# key_pads_sch_V3.net
KiCad netlist of a schematic drawn in Altium Designer
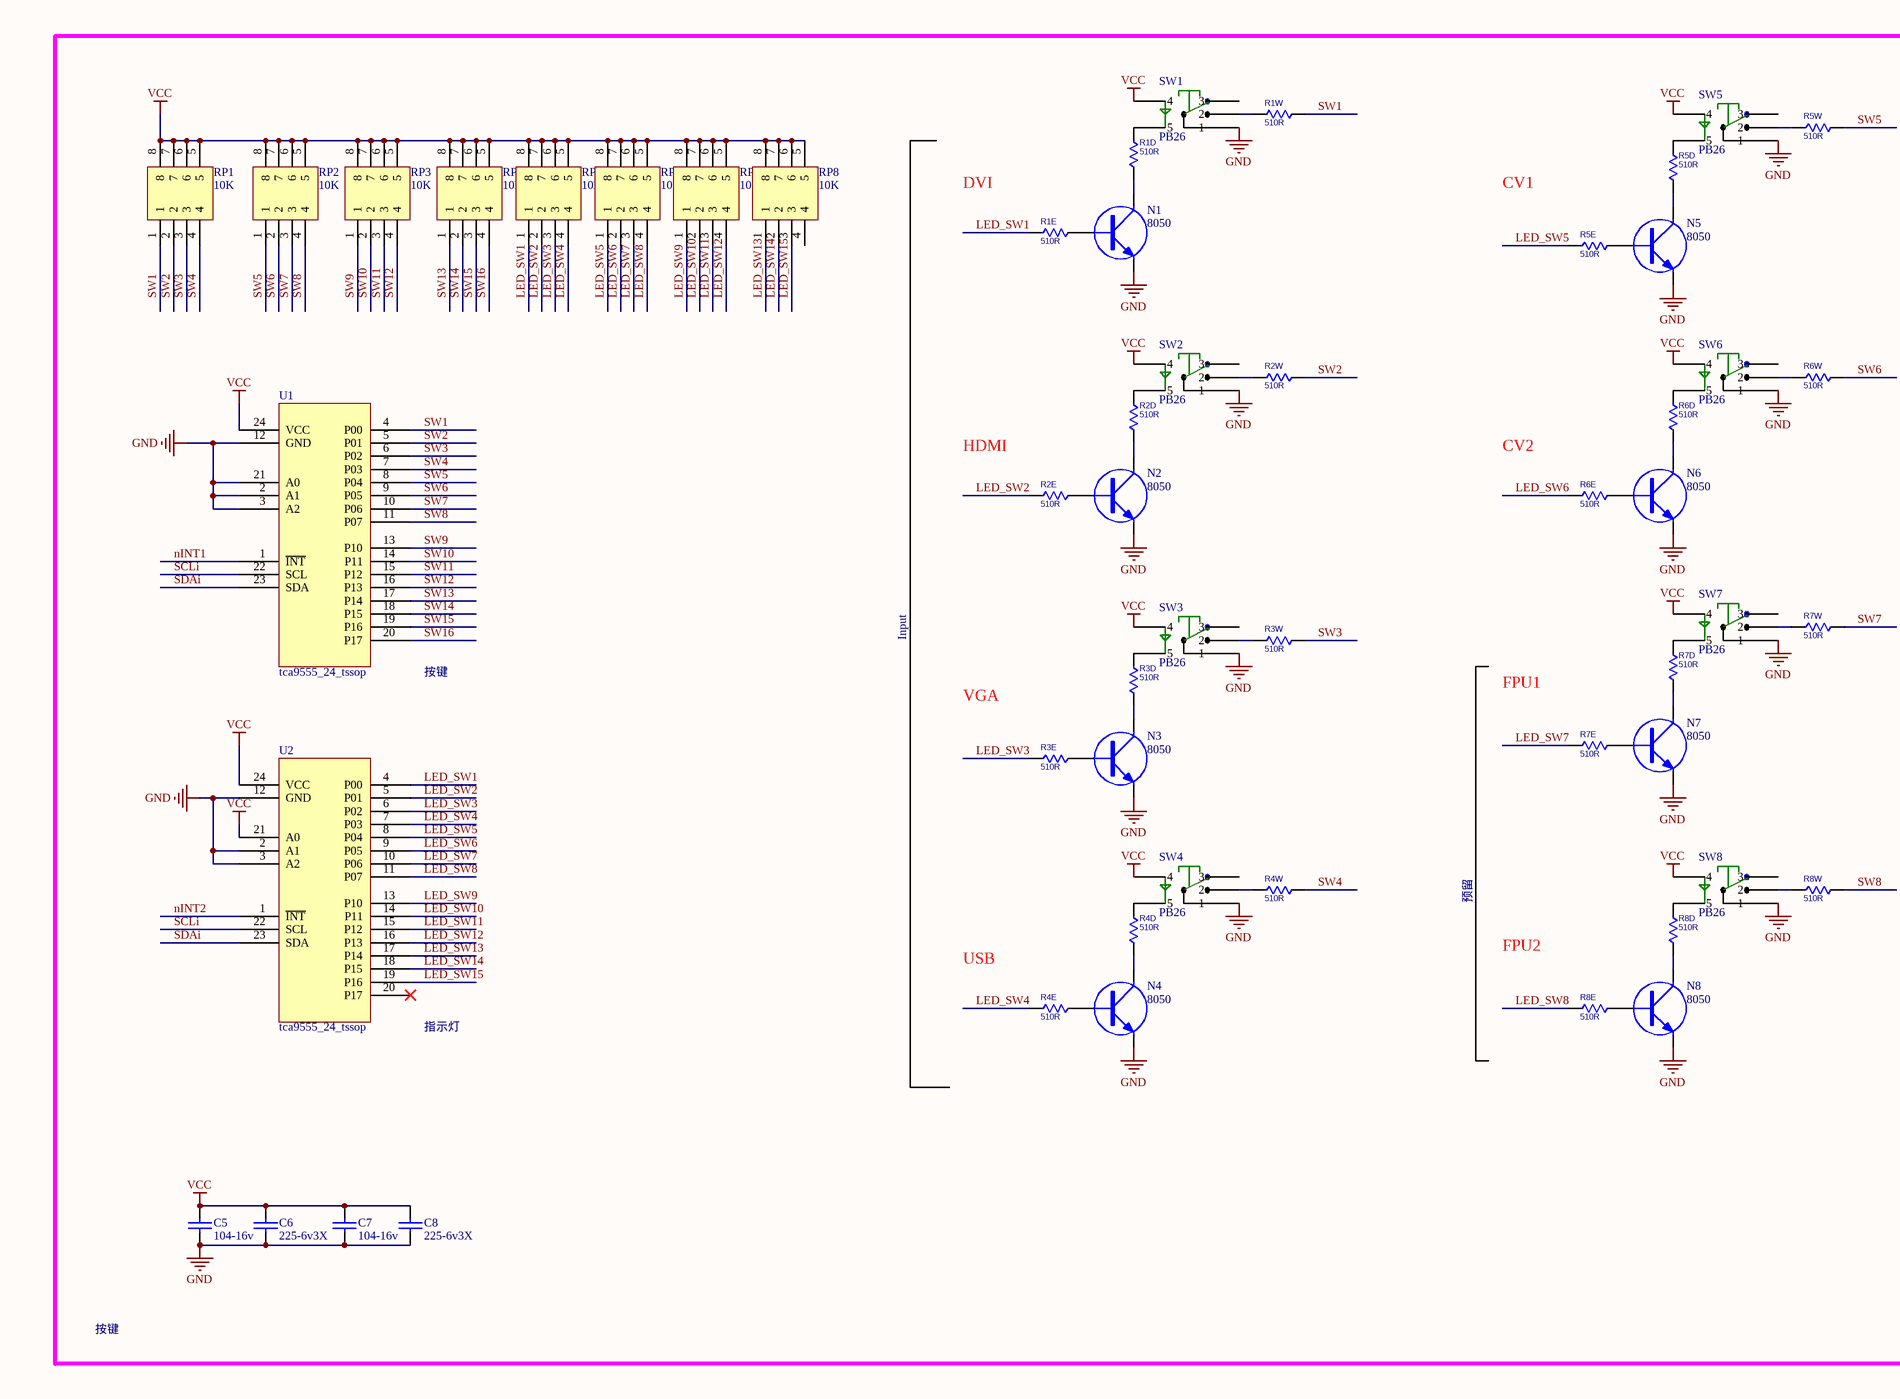
[diagram p0: key_pads_sch_V3.SchDoc, top left]
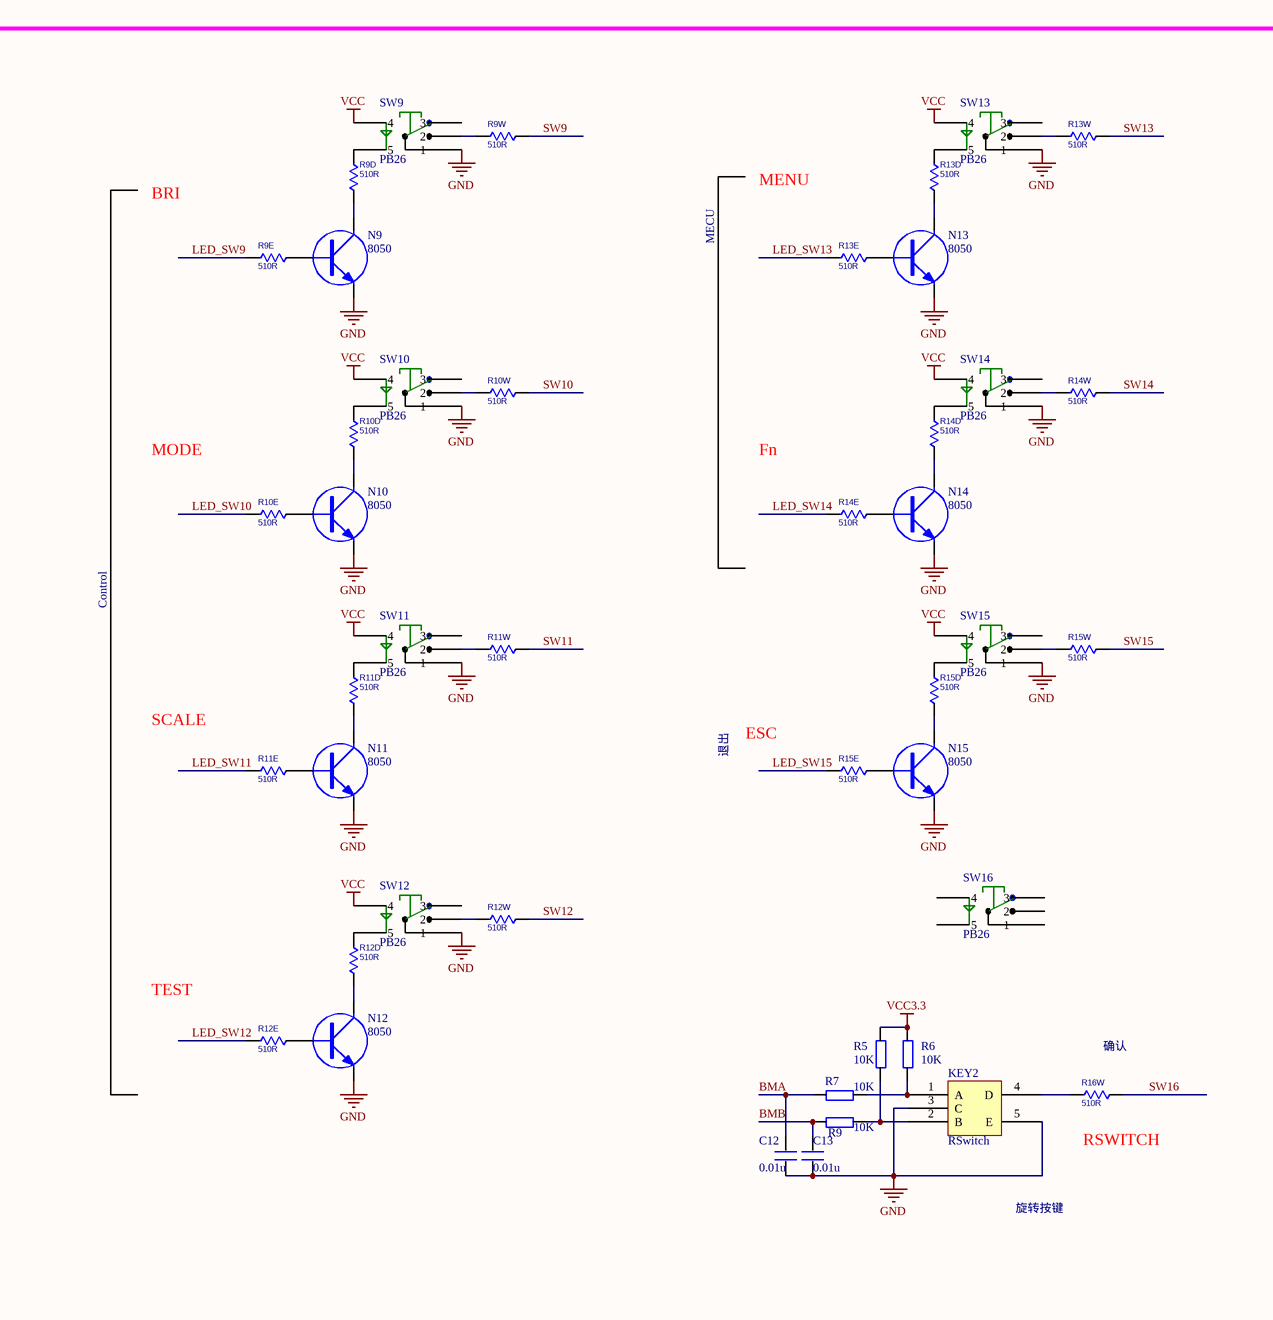
[diagram p1: key_pads_sch_V3.SchDoc, top right]
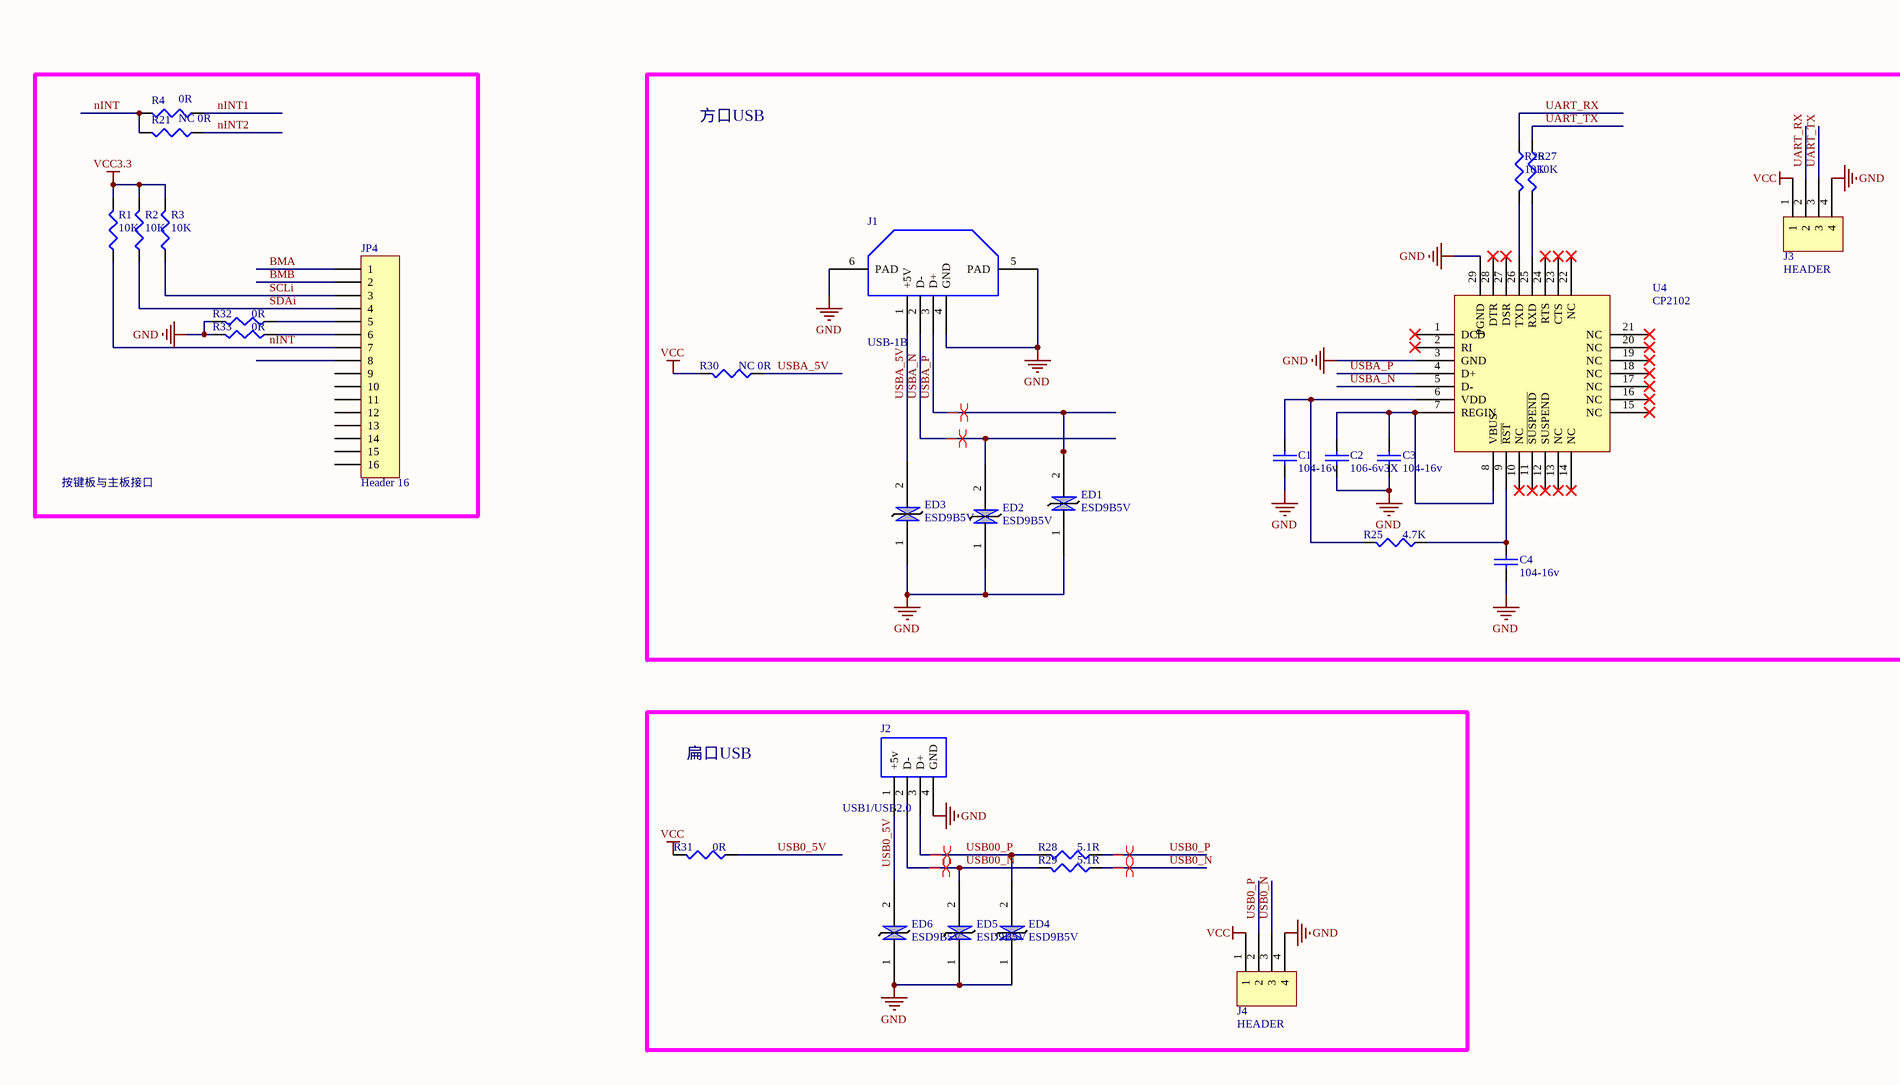
[diagram p2: key_pads_sch_V3.SchDoc, bottom left]
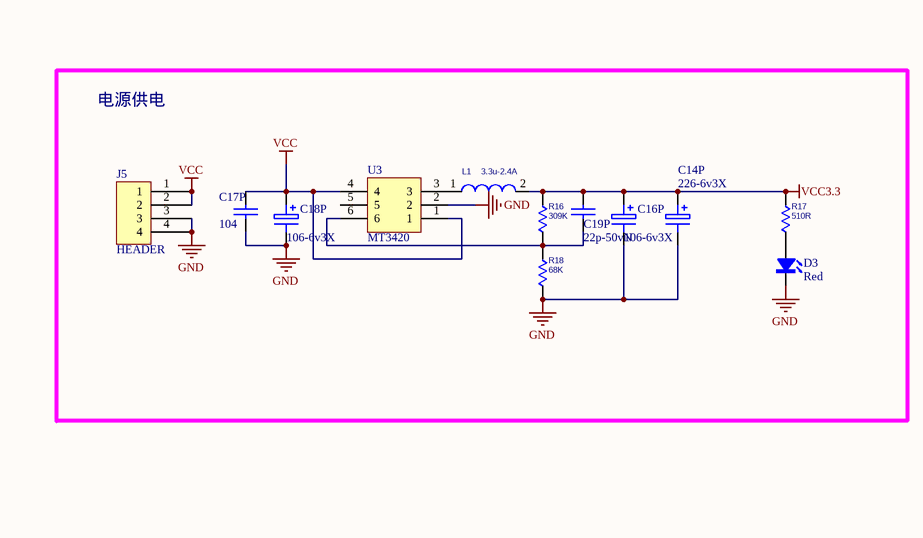
[diagram p3: key_pads_sch_V3.SchDoc, bottom right]

(export (version "E")
  (design (tool "Eeschema 10.0.6"))
  (components
    (comp (ref "C1") (value "104-16v") (footprint "C0402") (libsource (lib "MYLIBRARIES") (part "CAP")))
    (comp (ref "C2") (value "106-6v3X") (footprint "C0402") (libsource (lib "MYLIBRARIES") (part "CAP")))
    (comp (ref "C3") (value "104-16v") (footprint "C0402") (libsource (lib "MYLIBRARIES") (part "CAP")))
    (comp (ref "C4") (value "104-16v") (footprint "C0402") (libsource (lib "MYLIBRARIES") (part "CAP")))
    (comp (ref "C5") (value "104-16v") (footprint "C0402") (libsource (lib "MYLIBRARIES") (part "CAP")))
    (comp (ref "C6") (value "225-6v3X") (footprint "C0402") (libsource (lib "MYLIBRARIES") (part "CAP")))
    (comp (ref "C7") (value "104-16v") (footprint "C0402") (libsource (lib "MYLIBRARIES") (part "CAP")))
    (comp (ref "C8") (value "225-6v3X") (footprint "C0402") (libsource (lib "MYLIBRARIES") (part "CAP")))
    (comp (ref "C12") (value "0.01u") (footprint "R0402") (libsource (lib "MiniSTM32 V3.0封装库") (part "C")))
    (comp (ref "C13") (value "0.01u") (footprint "R0402") (libsource (lib "MiniSTM32 V3.0封装库") (part "C")))
    (comp (ref "C14P") (value "226-6v3X") (footprint "C0805") (libsource (lib "Monitor") (part "ELECTRO")))
    (comp (ref "C16P") (value "106-6v3X") (footprint "C0603") (libsource (lib "Monitor") (part "ELECTRO")))
    (comp (ref "C17P")
      (value "104")
      (footprint "C0402")
      (description "Capacitor")
      (libsource (lib "Monitor") (part "CAP"))
    )
    (comp (ref "C18P") (value "106-6v3X") (footprint "C0603") (libsource (lib "Monitor") (part "ELECTRO")))
    (comp (ref "C19P")
      (value "22p-50vN")
      (footprint "C0402")
      (description "Capacitor")
      (libsource (lib "Monitor") (part "CAP"))
    )
    (comp (ref "D3") (value "Red") (footprint "led0603") (libsource (lib "Monitor") (part "LED")))
    (comp (ref "ED1") (value "ESD9B5V") (footprint "E0402N") (libsource (lib "MYLIBRARIES") (part "ESD9B5V")))
    (comp (ref "ED2") (value "ESD9B5V") (footprint "E0402N") (libsource (lib "MYLIBRARIES") (part "ESD9B5V")))
    (comp (ref "ED3") (value "ESD9B5V") (footprint "E0402N") (libsource (lib "MYLIBRARIES") (part "ESD9B5V")))
    (comp (ref "ED4") (value "ESD9B5V") (footprint "E0402N") (libsource (lib "MYLIBRARIES") (part "ESD9B5V")))
    (comp (ref "ED5") (value "ESD9B5V") (footprint "E0402N") (libsource (lib "MYLIBRARIES") (part "ESD9B5V")))
    (comp (ref "ED6") (value "ESD9B5V") (footprint "E0402N") (libsource (lib "MYLIBRARIES") (part "ESD9B5V")))
    (comp (ref "J1")
      (value "USB-1B")
      (footprint "USB_BF_180")
      (libsource (lib "MYLIBRARIES") (part "USB-1B"))
    )
    (comp (ref "J2")
      (value "USB1/USB2.0")
      (footprint "USB_AF_180")
      (libsource (lib "MYLIBRARIES") (part "USB1/USB2.0"))
    )
    (comp (ref "J3") (value "HEADER") (footprint "SIP4-2.54") (libsource (lib "") (part "4PIN_1")))
    (comp (ref "J4") (value "HEADER") (footprint "SIP4-2.54") (libsource (lib "") (part "4PIN_1")))
    (comp (ref "J5") (value "HEADER") (footprint "SIP4-2.54") (libsource (lib "MYLIBRARIES") (part "4PIN")))
    (comp (ref "JP4")
      (value "Header 16")
      (footprint "DJ16J")
      (description "Header, 16-Pin")
      (fields (field (name "PUBLISHER") "Altium Limited"))
      (libsource (lib "MiniSTM32 V3.0封装库") (part "Header 16"))
    )
    (comp (ref "KEY2") (value "RSwitch") (footprint "RSwitch") (libsource (lib "Switch") (part "RSwitch")))
    (comp (ref "L1") (value "3.3u-2.4A") (footprint "L5040") (libsource (lib "Monitor") (part "L_Dup1")))
    (comp (ref "N1") (value "8050") (footprint "sot-23") (libsource (lib "MonitorV2") (part "NPN")))
    (comp (ref "N2") (value "8050") (footprint "sot-23") (libsource (lib "MonitorV2") (part "NPN")))
    (comp (ref "N3") (value "8050") (footprint "sot-23") (libsource (lib "MonitorV2") (part "NPN")))
    (comp (ref "N4") (value "8050") (footprint "sot-23") (libsource (lib "MonitorV2") (part "NPN")))
    (comp (ref "N5") (value "8050") (footprint "sot-23") (libsource (lib "MonitorV2") (part "NPN")))
    (comp (ref "N6") (value "8050") (footprint "sot-23") (libsource (lib "MonitorV2") (part "NPN")))
    (comp (ref "N7") (value "8050") (footprint "sot-23") (libsource (lib "MonitorV2") (part "NPN")))
    (comp (ref "N8") (value "8050") (footprint "sot-23") (libsource (lib "MonitorV2") (part "NPN")))
    (comp (ref "N9") (value "8050") (footprint "sot-23") (libsource (lib "MonitorV2") (part "NPN")))
    (comp (ref "N10") (value "8050") (footprint "sot-23") (libsource (lib "MonitorV2") (part "NPN")))
    (comp (ref "N11") (value "8050") (footprint "sot-23") (libsource (lib "MonitorV2") (part "NPN")))
    (comp (ref "N12") (value "8050") (footprint "sot-23") (libsource (lib "MonitorV2") (part "NPN")))
    (comp (ref "N13") (value "8050") (footprint "sot-23") (libsource (lib "MonitorV2") (part "NPN")))
    (comp (ref "N14") (value "8050") (footprint "sot-23") (libsource (lib "MonitorV2") (part "NPN")))
    (comp (ref "N15") (value "8050") (footprint "sot-23") (libsource (lib "MonitorV2") (part "NPN")))
    (comp (ref "R1") (value "10K") (footprint "R0402") (libsource (lib "MYLIBRARIES") (part "RES")))
    (comp (ref "R1D")
      (value "510R")
      (footprint "R0402")
      (description "RES 37.4 OHM 1/16W 1% 0402 SMD")
      (fields (field (name "DIGIKEY PART#") "541-37.4LCT-ND") (field (name "MANUFACTURER") "Vishay/Dale"))
      (libsource (lib "MonitorV2") (part "R"))
    )
    (comp (ref "R1E")
      (value "510R")
      (footprint "R0402")
      (description "RES 37.4 OHM 1/16W 1% 0402 SMD")
      (fields (field (name "DIGIKEY PART#") "541-37.4LCT-ND") (field (name "MANUFACTURER") "Vishay/Dale"))
      (libsource (lib "MonitorV2") (part "R"))
    )
    (comp (ref "R1W")
      (value "510R")
      (footprint "R0402")
      (description "RES 37.4 OHM 1/16W 1% 0402 SMD")
      (fields (field (name "DIGIKEY PART#") "541-37.4LCT-ND") (field (name "MANUFACTURER") "Vishay/Dale"))
      (libsource (lib "MonitorV2") (part "R"))
    )
    (comp (ref "R2") (value "10K") (footprint "R0402") (libsource (lib "MYLIBRARIES") (part "RES")))
    (comp (ref "R2D")
      (value "510R")
      (footprint "R0402")
      (description "RES 37.4 OHM 1/16W 1% 0402 SMD")
      (fields (field (name "DIGIKEY PART#") "541-37.4LCT-ND") (field (name "MANUFACTURER") "Vishay/Dale"))
      (libsource (lib "MonitorV2") (part "R"))
    )
    (comp (ref "R2E")
      (value "510R")
      (footprint "R0402")
      (description "RES 37.4 OHM 1/16W 1% 0402 SMD")
      (fields (field (name "DIGIKEY PART#") "541-37.4LCT-ND") (field (name "MANUFACTURER") "Vishay/Dale"))
      (libsource (lib "MonitorV2") (part "R"))
    )
    (comp (ref "R2W")
      (value "510R")
      (footprint "R0402")
      (description "RES 37.4 OHM 1/16W 1% 0402 SMD")
      (fields (field (name "DIGIKEY PART#") "541-37.4LCT-ND") (field (name "MANUFACTURER") "Vishay/Dale"))
      (libsource (lib "MonitorV2") (part "R"))
    )
    (comp (ref "R3") (value "10K") (footprint "R0402") (libsource (lib "MYLIBRARIES") (part "RES")))
    (comp (ref "R3D")
      (value "510R")
      (footprint "R0402")
      (description "RES 37.4 OHM 1/16W 1% 0402 SMD")
      (fields (field (name "DIGIKEY PART#") "541-37.4LCT-ND") (field (name "MANUFACTURER") "Vishay/Dale"))
      (libsource (lib "MonitorV2") (part "R"))
    )
    (comp (ref "R3E")
      (value "510R")
      (footprint "R0402")
      (description "RES 37.4 OHM 1/16W 1% 0402 SMD")
      (fields (field (name "DIGIKEY PART#") "541-37.4LCT-ND") (field (name "MANUFACTURER") "Vishay/Dale"))
      (libsource (lib "MonitorV2") (part "R"))
    )
    (comp (ref "R3W")
      (value "510R")
      (footprint "R0402")
      (description "RES 37.4 OHM 1/16W 1% 0402 SMD")
      (fields (field (name "DIGIKEY PART#") "541-37.4LCT-ND") (field (name "MANUFACTURER") "Vishay/Dale"))
      (libsource (lib "MonitorV2") (part "R"))
    )
    (comp (ref "R4") (value "0R") (footprint "R0402") (libsource (lib "MYLIBRARIES") (part "RES")))
    (comp (ref "R4D")
      (value "510R")
      (footprint "R0402")
      (description "RES 37.4 OHM 1/16W 1% 0402 SMD")
      (fields (field (name "DIGIKEY PART#") "541-37.4LCT-ND") (field (name "MANUFACTURER") "Vishay/Dale"))
      (libsource (lib "MonitorV2") (part "R"))
    )
    (comp (ref "R4E")
      (value "510R")
      (footprint "R0402")
      (description "RES 37.4 OHM 1/16W 1% 0402 SMD")
      (fields (field (name "DIGIKEY PART#") "541-37.4LCT-ND") (field (name "MANUFACTURER") "Vishay/Dale"))
      (libsource (lib "MonitorV2") (part "R"))
    )
    (comp (ref "R4W")
      (value "510R")
      (footprint "R0402")
      (description "RES 37.4 OHM 1/16W 1% 0402 SMD")
      (fields (field (name "DIGIKEY PART#") "541-37.4LCT-ND") (field (name "MANUFACTURER") "Vishay/Dale"))
      (libsource (lib "MonitorV2") (part "R"))
    )
    (comp (ref "R5") (value "10K") (footprint "R0402") (libsource (lib "MiniSTM32 V3.0封装库") (part "R")))
    (comp (ref "R5D")
      (value "510R")
      (footprint "R0402")
      (description "RES 37.4 OHM 1/16W 1% 0402 SMD")
      (fields (field (name "DIGIKEY PART#") "541-37.4LCT-ND") (field (name "MANUFACTURER") "Vishay/Dale"))
      (libsource (lib "MonitorV2") (part "R"))
    )
    (comp (ref "R5E")
      (value "510R")
      (footprint "R0402")
      (description "RES 37.4 OHM 1/16W 1% 0402 SMD")
      (fields (field (name "DIGIKEY PART#") "541-37.4LCT-ND") (field (name "MANUFACTURER") "Vishay/Dale"))
      (libsource (lib "MonitorV2") (part "R"))
    )
    (comp (ref "R5W")
      (value "510R")
      (footprint "R0402")
      (description "RES 37.4 OHM 1/16W 1% 0402 SMD")
      (fields (field (name "DIGIKEY PART#") "541-37.4LCT-ND") (field (name "MANUFACTURER") "Vishay/Dale"))
      (libsource (lib "MonitorV2") (part "R"))
    )
    (comp (ref "R6") (value "10K") (footprint "R0402") (libsource (lib "MiniSTM32 V3.0封装库") (part "R")))
    (comp (ref "R6D")
      (value "510R")
      (footprint "R0402")
      (description "RES 37.4 OHM 1/16W 1% 0402 SMD")
      (fields (field (name "DIGIKEY PART#") "541-37.4LCT-ND") (field (name "MANUFACTURER") "Vishay/Dale"))
      (libsource (lib "MonitorV2") (part "R"))
    )
    (comp (ref "R6E")
      (value "510R")
      (footprint "R0402")
      (description "RES 37.4 OHM 1/16W 1% 0402 SMD")
      (fields (field (name "DIGIKEY PART#") "541-37.4LCT-ND") (field (name "MANUFACTURER") "Vishay/Dale"))
      (libsource (lib "MonitorV2") (part "R"))
    )
    (comp (ref "R6W")
      (value "510R")
      (footprint "R0402")
      (description "RES 37.4 OHM 1/16W 1% 0402 SMD")
      (fields (field (name "DIGIKEY PART#") "541-37.4LCT-ND") (field (name "MANUFACTURER") "Vishay/Dale"))
      (libsource (lib "MonitorV2") (part "R"))
    )
    (comp (ref "R7") (value "10K") (footprint "R0402") (libsource (lib "MiniSTM32 V3.0封装库") (part "R")))
    (comp (ref "R7D")
      (value "510R")
      (footprint "R0402")
      (description "RES 37.4 OHM 1/16W 1% 0402 SMD")
      (fields (field (name "DIGIKEY PART#") "541-37.4LCT-ND") (field (name "MANUFACTURER") "Vishay/Dale"))
      (libsource (lib "MonitorV2") (part "R"))
    )
    (comp (ref "R7E")
      (value "510R")
      (footprint "R0402")
      (description "RES 37.4 OHM 1/16W 1% 0402 SMD")
      (fields (field (name "DIGIKEY PART#") "541-37.4LCT-ND") (field (name "MANUFACTURER") "Vishay/Dale"))
      (libsource (lib "MonitorV2") (part "R"))
    )
    (comp (ref "R7W")
      (value "510R")
      (footprint "R0402")
      (description "RES 37.4 OHM 1/16W 1% 0402 SMD")
      (fields (field (name "DIGIKEY PART#") "541-37.4LCT-ND") (field (name "MANUFACTURER") "Vishay/Dale"))
      (libsource (lib "MonitorV2") (part "R"))
    )
    (comp (ref "R8D")
      (value "510R")
      (footprint "R0402")
      (description "RES 37.4 OHM 1/16W 1% 0402 SMD")
      (fields (field (name "DIGIKEY PART#") "541-37.4LCT-ND") (field (name "MANUFACTURER") "Vishay/Dale"))
      (libsource (lib "MonitorV2") (part "R"))
    )
    (comp (ref "R8E")
      (value "510R")
      (footprint "R0402")
      (description "RES 37.4 OHM 1/16W 1% 0402 SMD")
      (fields (field (name "DIGIKEY PART#") "541-37.4LCT-ND") (field (name "MANUFACTURER") "Vishay/Dale"))
      (libsource (lib "MonitorV2") (part "R"))
    )
    (comp (ref "R8W")
      (value "510R")
      (footprint "R0402")
      (description "RES 37.4 OHM 1/16W 1% 0402 SMD")
      (fields (field (name "DIGIKEY PART#") "541-37.4LCT-ND") (field (name "MANUFACTURER") "Vishay/Dale"))
      (libsource (lib "MonitorV2") (part "R"))
    )
    (comp (ref "R9") (value "10K") (footprint "R0402") (libsource (lib "MiniSTM32 V3.0封装库") (part "R")))
    (comp (ref "R9D")
      (value "510R")
      (footprint "R0402")
      (description "RES 37.4 OHM 1/16W 1% 0402 SMD")
      (fields (field (name "DIGIKEY PART#") "541-37.4LCT-ND") (field (name "MANUFACTURER") "Vishay/Dale"))
      (libsource (lib "MonitorV2") (part "R"))
    )
    (comp (ref "R9E")
      (value "510R")
      (footprint "R0402")
      (description "RES 37.4 OHM 1/16W 1% 0402 SMD")
      (fields (field (name "DIGIKEY PART#") "541-37.4LCT-ND") (field (name "MANUFACTURER") "Vishay/Dale"))
      (libsource (lib "MonitorV2") (part "R"))
    )
    (comp (ref "R9W")
      (value "510R")
      (footprint "R0402")
      (description "RES 37.4 OHM 1/16W 1% 0402 SMD")
      (fields (field (name "DIGIKEY PART#") "541-37.4LCT-ND") (field (name "MANUFACTURER") "Vishay/Dale"))
      (libsource (lib "MonitorV2") (part "R"))
    )
    (comp (ref "R10D")
      (value "510R")
      (footprint "R0402")
      (description "RES 37.4 OHM 1/16W 1% 0402 SMD")
      (fields (field (name "DIGIKEY PART#") "541-37.4LCT-ND") (field (name "MANUFACTURER") "Vishay/Dale"))
      (libsource (lib "MonitorV2") (part "R"))
    )
    (comp (ref "R10E")
      (value "510R")
      (footprint "R0402")
      (description "RES 37.4 OHM 1/16W 1% 0402 SMD")
      (fields (field (name "DIGIKEY PART#") "541-37.4LCT-ND") (field (name "MANUFACTURER") "Vishay/Dale"))
      (libsource (lib "MonitorV2") (part "R"))
    )
    (comp (ref "R10W")
      (value "510R")
      (footprint "R0402")
      (description "RES 37.4 OHM 1/16W 1% 0402 SMD")
      (fields (field (name "DIGIKEY PART#") "541-37.4LCT-ND") (field (name "MANUFACTURER") "Vishay/Dale"))
      (libsource (lib "MonitorV2") (part "R"))
    )
    (comp (ref "R11D")
      (value "510R")
      (footprint "R0402")
      (description "RES 37.4 OHM 1/16W 1% 0402 SMD")
      (fields (field (name "DIGIKEY PART#") "541-37.4LCT-ND") (field (name "MANUFACTURER") "Vishay/Dale"))
      (libsource (lib "MonitorV2") (part "R"))
    )
    (comp (ref "R11E")
      (value "510R")
      (footprint "R0402")
      (description "RES 37.4 OHM 1/16W 1% 0402 SMD")
      (fields (field (name "DIGIKEY PART#") "541-37.4LCT-ND") (field (name "MANUFACTURER") "Vishay/Dale"))
      (libsource (lib "MonitorV2") (part "R"))
    )
    (comp (ref "R11W")
      (value "510R")
      (footprint "R0402")
      (description "RES 37.4 OHM 1/16W 1% 0402 SMD")
      (fields (field (name "DIGIKEY PART#") "541-37.4LCT-ND") (field (name "MANUFACTURER") "Vishay/Dale"))
      (libsource (lib "MonitorV2") (part "R"))
    )
    (comp (ref "R12D")
      (value "510R")
      (footprint "R0402")
      (description "RES 37.4 OHM 1/16W 1% 0402 SMD")
      (fields (field (name "DIGIKEY PART#") "541-37.4LCT-ND") (field (name "MANUFACTURER") "Vishay/Dale"))
      (libsource (lib "MonitorV2") (part "R"))
    )
    (comp (ref "R12E")
      (value "510R")
      (footprint "R0402")
      (description "RES 37.4 OHM 1/16W 1% 0402 SMD")
      (fields (field (name "DIGIKEY PART#") "541-37.4LCT-ND") (field (name "MANUFACTURER") "Vishay/Dale"))
      (libsource (lib "MonitorV2") (part "R"))
    )
    (comp (ref "R12W")
      (value "510R")
      (footprint "R0402")
      (description "RES 37.4 OHM 1/16W 1% 0402 SMD")
      (fields (field (name "DIGIKEY PART#") "541-37.4LCT-ND") (field (name "MANUFACTURER") "Vishay/Dale"))
      (libsource (lib "MonitorV2") (part "R"))
    )
    (comp (ref "R13D")
      (value "510R")
      (footprint "R0402")
      (description "RES 37.4 OHM 1/16W 1% 0402 SMD")
      (fields (field (name "DIGIKEY PART#") "541-37.4LCT-ND") (field (name "MANUFACTURER") "Vishay/Dale"))
      (libsource (lib "MonitorV2") (part "R"))
    )
    (comp (ref "R13E")
      (value "510R")
      (footprint "R0402")
      (description "RES 37.4 OHM 1/16W 1% 0402 SMD")
      (fields (field (name "DIGIKEY PART#") "541-37.4LCT-ND") (field (name "MANUFACTURER") "Vishay/Dale"))
      (libsource (lib "MonitorV2") (part "R"))
    )
    (comp (ref "R13W")
      (value "510R")
      (footprint "R0402")
      (description "RES 37.4 OHM 1/16W 1% 0402 SMD")
      (fields (field (name "DIGIKEY PART#") "541-37.4LCT-ND") (field (name "MANUFACTURER") "Vishay/Dale"))
      (libsource (lib "MonitorV2") (part "R"))
    )
    (comp (ref "R14D")
      (value "510R")
      (footprint "R0402")
      (description "RES 37.4 OHM 1/16W 1% 0402 SMD")
      (fields (field (name "DIGIKEY PART#") "541-37.4LCT-ND") (field (name "MANUFACTURER") "Vishay/Dale"))
      (libsource (lib "MonitorV2") (part "R"))
    )
    (comp (ref "R14E")
      (value "510R")
      (footprint "R0402")
      (description "RES 37.4 OHM 1/16W 1% 0402 SMD")
      (fields (field (name "DIGIKEY PART#") "541-37.4LCT-ND") (field (name "MANUFACTURER") "Vishay/Dale"))
      (libsource (lib "MonitorV2") (part "R"))
    )
    (comp (ref "R14W")
      (value "510R")
      (footprint "R0402")
      (description "RES 37.4 OHM 1/16W 1% 0402 SMD")
      (fields (field (name "DIGIKEY PART#") "541-37.4LCT-ND") (field (name "MANUFACTURER") "Vishay/Dale"))
      (libsource (lib "MonitorV2") (part "R"))
    )
    (comp (ref "R15D")
      (value "510R")
      (footprint "R0402")
      (description "RES 37.4 OHM 1/16W 1% 0402 SMD")
      (fields (field (name "DIGIKEY PART#") "541-37.4LCT-ND") (field (name "MANUFACTURER") "Vishay/Dale"))
      (libsource (lib "MonitorV2") (part "R"))
    )
    (comp (ref "R15E")
      (value "510R")
      (footprint "R0402")
      (description "RES 37.4 OHM 1/16W 1% 0402 SMD")
      (fields (field (name "DIGIKEY PART#") "541-37.4LCT-ND") (field (name "MANUFACTURER") "Vishay/Dale"))
      (libsource (lib "MonitorV2") (part "R"))
    )
    (comp (ref "R15W")
      (value "510R")
      (footprint "R0402")
      (description "RES 37.4 OHM 1/16W 1% 0402 SMD")
      (fields (field (name "DIGIKEY PART#") "541-37.4LCT-ND") (field (name "MANUFACTURER") "Vishay/Dale"))
      (libsource (lib "MonitorV2") (part "R"))
    )
    (comp (ref "R16")
      (value "309K")
      (footprint "R0402")
      (description "RES 37.4 OHM 1/16W 1% 0402 SMD")
      (fields (field (name "DIGIKEY PART#") "541-37.4LCT-ND") (field (name "MANUFACTURER") "Vishay/Dale"))
      (libsource (lib "Monitor") (part "R"))
    )
    (comp (ref "R16W")
      (value "510R")
      (footprint "R0402")
      (description "RES 37.4 OHM 1/16W 1% 0402 SMD")
      (fields (field (name "DIGIKEY PART#") "541-37.4LCT-ND") (field (name "MANUFACTURER") "Vishay/Dale"))
      (libsource (lib "MonitorV2") (part "R"))
    )
    (comp (ref "R17")
      (value "510R")
      (footprint "R0402")
      (description "RES 37.4 OHM 1/16W 1% 0402 SMD")
      (fields (field (name "DIGIKEY PART#") "541-37.4LCT-ND") (field (name "MANUFACTURER") "Vishay/Dale"))
      (libsource (lib "Monitor") (part "R"))
    )
    (comp (ref "R18")
      (value "68K")
      (footprint "R0402")
      (description "RES 37.4 OHM 1/16W 1% 0402 SMD")
      (fields (field (name "DIGIKEY PART#") "541-37.4LCT-ND") (field (name "MANUFACTURER") "Vishay/Dale"))
      (libsource (lib "Monitor") (part "R"))
    )
    (comp (ref "R21") (value "NC 0R") (footprint "R0402") (libsource (lib "MYLIBRARIES") (part "RES")))
    (comp (ref "R25") (value "4.7K") (footprint "R0402") (libsource (lib "MYLIBRARIES") (part "RES")))
    (comp (ref "R26") (value "10K") (footprint "R0402") (libsource (lib "MYLIBRARIES") (part "RES")))
    (comp (ref "R27") (value "10K") (footprint "R0402") (libsource (lib "MYLIBRARIES") (part "RES")))
    (comp (ref "R28") (value "5.1R") (footprint "R0402") (libsource (lib "MYLIBRARIES") (part "RES")))
    (comp (ref "R29") (value "5.1R") (footprint "R0402") (libsource (lib "MYLIBRARIES") (part "RES")))
    (comp (ref "R30") (value "NC 0R") (footprint "R0402") (libsource (lib "MYLIBRARIES") (part "RES")))
    (comp (ref "R31") (value "0R") (footprint "R0402") (libsource (lib "MYLIBRARIES") (part "RES")))
    (comp (ref "R32") (value "0R") (footprint "R0402") (libsource (lib "MYLIBRARIES") (part "RES")))
    (comp (ref "R33") (value "0R") (footprint "R0402") (libsource (lib "MYLIBRARIES") (part "RES")))
    (comp (ref "RP1") (value "10K") (footprint "40402") (libsource (lib "MYLIBRARIES") (part "DIP8")))
    (comp (ref "RP2") (value "10K") (footprint "40402") (libsource (lib "MYLIBRARIES") (part "DIP8")))
    (comp (ref "RP3") (value "10K") (footprint "40402") (libsource (lib "MYLIBRARIES") (part "DIP8")))
    (comp (ref "RP4") (value "10K") (footprint "40402") (libsource (lib "MYLIBRARIES") (part "DIP8")))
    (comp (ref "RP5") (value "10K") (footprint "40402") (libsource (lib "MYLIBRARIES") (part "DIP8")))
    (comp (ref "RP6") (value "10K") (footprint "40402") (libsource (lib "MYLIBRARIES") (part "DIP8")))
    (comp (ref "RP7") (value "10K") (footprint "40402") (libsource (lib "MYLIBRARIES") (part "DIP8")))
    (comp (ref "RP8") (value "10K") (footprint "40402") (libsource (lib "MYLIBRARIES") (part "DIP8")))
    (comp (ref "SW1") (value "PB26") (footprint "PB26") (libsource (lib "Switch") (part "PB26")))
    (comp (ref "SW2") (value "PB26") (footprint "PB26") (libsource (lib "Switch") (part "PB26")))
    (comp (ref "SW3") (value "PB26") (footprint "PB26") (libsource (lib "Switch") (part "PB26")))
    (comp (ref "SW4") (value "PB26") (footprint "PB26") (libsource (lib "Switch") (part "PB26")))
    (comp (ref "SW5") (value "PB26") (footprint "PB26") (libsource (lib "Switch") (part "PB26")))
    (comp (ref "SW6") (value "PB26") (footprint "PB26") (libsource (lib "Switch") (part "PB26")))
    (comp (ref "SW7") (value "PB26") (footprint "PB26") (libsource (lib "Switch") (part "PB26")))
    (comp (ref "SW8") (value "PB26") (footprint "PB26") (libsource (lib "Switch") (part "PB26")))
    (comp (ref "SW9") (value "PB26") (footprint "PB26") (libsource (lib "Switch") (part "PB26")))
    (comp (ref "SW10") (value "PB26") (footprint "PB26") (libsource (lib "Switch") (part "PB26")))
    (comp (ref "SW11") (value "PB26") (footprint "PB26") (libsource (lib "Switch") (part "PB26")))
    (comp (ref "SW12") (value "PB26") (footprint "PB26") (libsource (lib "Switch") (part "PB26")))
    (comp (ref "SW13") (value "PB26") (footprint "PB26") (libsource (lib "Switch") (part "PB26")))
    (comp (ref "SW14") (value "PB26") (footprint "PB26") (libsource (lib "Switch") (part "PB26")))
    (comp (ref "SW15") (value "PB26") (footprint "PB26") (libsource (lib "Switch") (part "PB26")))
    (comp (ref "SW16") (value "PB26") (footprint "PB26") (libsource (lib "Switch") (part "PB26")))
    (comp (ref "U1")
      (value "tca9555_24_tssop")
      (footprint "TSSOP24_TCA9555")
      (libsource (lib "MYLIBRARIES") (part "tca9555_24_tssop"))
    )
    (comp (ref "U2")
      (value "tca9555_24_tssop")
      (footprint "TSSOP24_TCA9555")
      (libsource (lib "MYLIBRARIES") (part "tca9555_24_tssop"))
    )
    (comp (ref "U3") (value "MT3420") (footprint "SOT26") (libsource (lib "Monitor") (part "DIP6")))
    (comp (ref "U4")
      (value "CP2102")
      (footprint "QFN28_CP2102")
      (libsource (lib "MYLIBRARIES") (part "CP2102"))
    )
  )
  (nets
    (net (code "1") (name "/BMA") (class "Default")
      (node (ref "C12") (pin "2") (pintype "passive"))
      (node (ref "JP4") (pin "1") (pinfunction "1_1") (pintype "passive"))
      (node (ref "R7") (pin "1") (pintype "passive"))
    )
    (net (code "2") (name "/BMB") (class "Default")
      (node (ref "C13") (pin "2") (pintype "passive"))
      (node (ref "JP4") (pin "2") (pinfunction "2_2") (pintype "passive"))
      (node (ref "R9") (pin "1") (pintype "passive"))
    )
    (net (code "3") (name "/LED_SW1") (class "Default")
      (node (ref "R1E") (pin "1") (pinfunction "1_1") (pintype "passive"))
      (node (ref "RP5") (pin "1") (pinfunction "1_1") (pintype "passive"))
      (node (ref "U2") (pin "4") (pinfunction "P00_4") (pintype "passive"))
    )
    (net (code "4") (name "/LED_SW2") (class "Default")
      (node (ref "R2E") (pin "1") (pinfunction "1_1") (pintype "passive"))
      (node (ref "RP5") (pin "2") (pinfunction "2_2") (pintype "passive"))
      (node (ref "U2") (pin "5") (pinfunction "P01_5") (pintype "passive"))
    )
    (net (code "5") (name "/LED_SW3") (class "Default")
      (node (ref "R3E") (pin "1") (pinfunction "1_1") (pintype "passive"))
      (node (ref "RP5") (pin "3") (pinfunction "3_3") (pintype "passive"))
      (node (ref "U2") (pin "6") (pinfunction "P02_6") (pintype "passive"))
    )
    (net (code "6") (name "/LED_SW4") (class "Default")
      (node (ref "R4E") (pin "1") (pinfunction "1_1") (pintype "passive"))
      (node (ref "RP5") (pin "4") (pinfunction "4_4") (pintype "passive"))
      (node (ref "U2") (pin "7") (pinfunction "P03_7") (pintype "passive"))
    )
    (net (code "7") (name "/LED_SW5") (class "Default")
      (node (ref "R5E") (pin "1") (pinfunction "1_1") (pintype "passive"))
      (node (ref "RP6") (pin "1") (pinfunction "1_1") (pintype "passive"))
      (node (ref "U2") (pin "8") (pinfunction "P04_8") (pintype "passive"))
    )
    (net (code "8") (name "/LED_SW6") (class "Default")
      (node (ref "R6E") (pin "1") (pinfunction "1_1") (pintype "passive"))
      (node (ref "RP6") (pin "2") (pinfunction "2_2") (pintype "passive"))
      (node (ref "U2") (pin "9") (pinfunction "P05_9") (pintype "passive"))
    )
    (net (code "9") (name "/LED_SW7") (class "Default")
      (node (ref "R7E") (pin "1") (pinfunction "1_1") (pintype "passive"))
      (node (ref "RP6") (pin "3") (pinfunction "3_3") (pintype "passive"))
      (node (ref "U2") (pin "10") (pinfunction "P06_10") (pintype "passive"))
    )
    (net (code "10") (name "/LED_SW8") (class "Default")
      (node (ref "R8E") (pin "1") (pinfunction "1_1") (pintype "passive"))
      (node (ref "RP6") (pin "4") (pinfunction "4_4") (pintype "passive"))
      (node (ref "U2") (pin "11") (pinfunction "P07_11") (pintype "passive"))
    )
    (net (code "11") (name "/LED_SW9") (class "Default")
      (node (ref "R9E") (pin "1") (pinfunction "1_1") (pintype "passive"))
      (node (ref "RP7") (pin "1") (pinfunction "1_1") (pintype "passive"))
      (node (ref "U2") (pin "13") (pinfunction "P10_13") (pintype "passive"))
    )
    (net (code "12") (name "/LED_SW10") (class "Default")
      (node (ref "R10E") (pin "1") (pinfunction "1_1") (pintype "passive"))
      (node (ref "RP7") (pin "2") (pinfunction "2_2") (pintype "passive"))
      (node (ref "U2") (pin "14") (pinfunction "P11_14") (pintype "passive"))
    )
    (net (code "13") (name "/LED_SW11") (class "Default")
      (node (ref "R11E") (pin "1") (pinfunction "1_1") (pintype "passive"))
      (node (ref "RP7") (pin "3") (pinfunction "3_3") (pintype "passive"))
      (node (ref "U2") (pin "15") (pinfunction "P12_15") (pintype "passive"))
    )
    (net (code "14") (name "/LED_SW12") (class "Default")
      (node (ref "R12E") (pin "1") (pinfunction "1_1") (pintype "passive"))
      (node (ref "RP7") (pin "4") (pinfunction "4_4") (pintype "passive"))
      (node (ref "U2") (pin "16") (pinfunction "P13_16") (pintype "passive"))
    )
    (net (code "15") (name "/LED_SW13") (class "Default")
      (node (ref "R13E") (pin "1") (pinfunction "1_1") (pintype "passive"))
      (node (ref "RP8") (pin "1") (pinfunction "1_1") (pintype "passive"))
      (node (ref "U2") (pin "17") (pinfunction "P14_17") (pintype "passive"))
    )
    (net (code "16") (name "/LED_SW14") (class "Default")
      (node (ref "R14E") (pin "1") (pinfunction "1_1") (pintype "passive"))
      (node (ref "RP8") (pin "2") (pinfunction "2_2") (pintype "passive"))
      (node (ref "U2") (pin "18") (pinfunction "P15_18") (pintype "passive"))
    )
    (net (code "17") (name "/LED_SW15") (class "Default")
      (node (ref "R15E") (pin "1") (pinfunction "1_1") (pintype "passive"))
      (node (ref "RP8") (pin "3") (pinfunction "3_3") (pintype "passive"))
      (node (ref "U2") (pin "19") (pinfunction "P16_19") (pintype "passive"))
    )
    (net (code "18") (name "/SCLi") (class "Default")
      (node (ref "JP4") (pin "3") (pinfunction "3_3") (pintype "passive"))
      (node (ref "R3") (pin "1") (pinfunction "1_1") (pintype "passive"))
      (node (ref "U1") (pin "22") (pinfunction "SCL_22") (pintype "passive"))
      (node (ref "U2") (pin "22") (pinfunction "SCL_22") (pintype "passive"))
    )
    (net (code "19") (name "/SDAi") (class "Default")
      (node (ref "JP4") (pin "4") (pinfunction "4_4") (pintype "passive"))
      (node (ref "R2") (pin "1") (pinfunction "1_1") (pintype "passive"))
      (node (ref "U1") (pin "23") (pinfunction "SDA_23") (pintype "passive"))
      (node (ref "U2") (pin "23") (pinfunction "SDA_23") (pintype "passive"))
    )
    (net (code "20") (name "/SW1") (class "Default")
      (node (ref "R1W") (pin "2") (pinfunction "2_2") (pintype "passive"))
      (node (ref "RP1") (pin "1") (pinfunction "1_1") (pintype "passive"))
      (node (ref "U1") (pin "4") (pinfunction "P00_4") (pintype "passive"))
    )
    (net (code "21") (name "/SW2") (class "Default")
      (node (ref "R2W") (pin "2") (pinfunction "2_2") (pintype "passive"))
      (node (ref "RP1") (pin "2") (pinfunction "2_2") (pintype "passive"))
      (node (ref "U1") (pin "5") (pinfunction "P01_5") (pintype "passive"))
    )
    (net (code "22") (name "/SW3") (class "Default")
      (node (ref "R3W") (pin "2") (pinfunction "2_2") (pintype "passive"))
      (node (ref "RP1") (pin "3") (pinfunction "3_3") (pintype "passive"))
      (node (ref "U1") (pin "6") (pinfunction "P02_6") (pintype "passive"))
    )
    (net (code "23") (name "/SW4") (class "Default")
      (node (ref "R4W") (pin "2") (pinfunction "2_2") (pintype "passive"))
      (node (ref "RP1") (pin "4") (pinfunction "4_4") (pintype "passive"))
      (node (ref "U1") (pin "7") (pinfunction "P03_7") (pintype "passive"))
    )
    (net (code "24") (name "/SW5") (class "Default")
      (node (ref "R5W") (pin "2") (pinfunction "2_2") (pintype "passive"))
      (node (ref "RP2") (pin "1") (pinfunction "1_1") (pintype "passive"))
      (node (ref "U1") (pin "8") (pinfunction "P04_8") (pintype "passive"))
    )
    (net (code "25") (name "/SW6") (class "Default")
      (node (ref "R6W") (pin "2") (pinfunction "2_2") (pintype "passive"))
      (node (ref "RP2") (pin "2") (pinfunction "2_2") (pintype "passive"))
      (node (ref "U1") (pin "9") (pinfunction "P05_9") (pintype "passive"))
    )
    (net (code "26") (name "/SW7") (class "Default")
      (node (ref "R7W") (pin "2") (pinfunction "2_2") (pintype "passive"))
      (node (ref "RP2") (pin "3") (pinfunction "3_3") (pintype "passive"))
      (node (ref "U1") (pin "10") (pinfunction "P06_10") (pintype "passive"))
    )
    (net (code "27") (name "/SW8") (class "Default")
      (node (ref "R8W") (pin "2") (pinfunction "2_2") (pintype "passive"))
      (node (ref "RP2") (pin "4") (pinfunction "4_4") (pintype "passive"))
      (node (ref "U1") (pin "11") (pinfunction "P07_11") (pintype "passive"))
    )
    (net (code "28") (name "/SW9") (class "Default")
      (node (ref "R9W") (pin "2") (pinfunction "2_2") (pintype "passive"))
      (node (ref "RP3") (pin "1") (pinfunction "1_1") (pintype "passive"))
      (node (ref "U1") (pin "13") (pinfunction "P10_13") (pintype "passive"))
    )
    (net (code "29") (name "/SW10") (class "Default")
      (node (ref "R10W") (pin "2") (pinfunction "2_2") (pintype "passive"))
      (node (ref "RP3") (pin "2") (pinfunction "2_2") (pintype "passive"))
      (node (ref "U1") (pin "14") (pinfunction "P11_14") (pintype "passive"))
    )
    (net (code "30") (name "/SW11") (class "Default")
      (node (ref "R11W") (pin "2") (pinfunction "2_2") (pintype "passive"))
      (node (ref "RP3") (pin "3") (pinfunction "3_3") (pintype "passive"))
      (node (ref "U1") (pin "15") (pinfunction "P12_15") (pintype "passive"))
    )
    (net (code "31") (name "/SW12") (class "Default")
      (node (ref "R12W") (pin "2") (pinfunction "2_2") (pintype "passive"))
      (node (ref "RP3") (pin "4") (pinfunction "4_4") (pintype "passive"))
      (node (ref "U1") (pin "16") (pinfunction "P13_16") (pintype "passive"))
    )
    (net (code "32") (name "/SW13") (class "Default")
      (node (ref "R13W") (pin "2") (pinfunction "2_2") (pintype "passive"))
      (node (ref "RP4") (pin "1") (pinfunction "1_1") (pintype "passive"))
      (node (ref "U1") (pin "17") (pinfunction "P14_17") (pintype "passive"))
    )
    (net (code "33") (name "/SW14") (class "Default")
      (node (ref "R14W") (pin "2") (pinfunction "2_2") (pintype "passive"))
      (node (ref "RP4") (pin "2") (pinfunction "2_2") (pintype "passive"))
      (node (ref "U1") (pin "18") (pinfunction "P15_18") (pintype "passive"))
    )
    (net (code "34") (name "/SW15") (class "Default")
      (node (ref "R15W") (pin "2") (pinfunction "2_2") (pintype "passive"))
      (node (ref "RP4") (pin "3") (pinfunction "3_3") (pintype "passive"))
      (node (ref "U1") (pin "19") (pinfunction "P16_19") (pintype "passive"))
    )
    (net (code "35") (name "/SW16") (class "Default")
      (node (ref "R16W") (pin "2") (pinfunction "2_2") (pintype "passive"))
      (node (ref "RP4") (pin "4") (pinfunction "4_4") (pintype "passive"))
      (node (ref "U1") (pin "20") (pinfunction "P17_20") (pintype "passive"))
    )
    (net (code "36") (name "/UART_RX") (class "Default")
      (node (ref "J3") (pin "2") (pinfunction "2_2") (pintype "passive"))
      (node (ref "R26") (pin "1") (pinfunction "1_1") (pintype "passive"))
    )
    (net (code "37") (name "/UART_TX") (class "Default")
      (node (ref "J3") (pin "3") (pinfunction "3_3") (pintype "passive"))
      (node (ref "R27") (pin "1") (pinfunction "1_1") (pintype "passive"))
    )
    (net (code "38") (name "/USB0_5V") (class "Default")
      (node (ref "ED6") (pin "2") (pinfunction "2_2") (pintype "passive"))
      (node (ref "J2") (pin "1") (pinfunction "+5v_1") (pintype "passive"))
      (node (ref "R31") (pin "1") (pinfunction "1_1") (pintype "passive"))
    )
    (net (code "39") (name "/USB0_N") (class "Default")
      (node (ref "J4") (pin "3") (pinfunction "3_3") (pintype "passive"))
      (node (ref "R29") (pin "1") (pinfunction "1_1") (pintype "passive"))
    )
    (net (code "40") (name "/USB00_N") (class "Default")
      (node (ref "ED5") (pin "2") (pinfunction "2_2") (pintype "passive"))
      (node (ref "J2") (pin "2") (pinfunction "D-_2") (pintype "passive"))
      (node (ref "R29") (pin "2") (pinfunction "2_2") (pintype "passive"))
    )
    (net (code "41") (name "/USB0_P") (class "Default")
      (node (ref "J4") (pin "2") (pinfunction "2_2") (pintype "passive"))
      (node (ref "R28") (pin "1") (pinfunction "1_1") (pintype "passive"))
    )
    (net (code "42") (name "/USB00_P") (class "Default")
      (node (ref "ED4") (pin "2") (pinfunction "2_2") (pintype "passive"))
      (node (ref "J2") (pin "3") (pinfunction "D+_3") (pintype "passive"))
      (node (ref "R28") (pin "2") (pinfunction "2_2") (pintype "passive"))
    )
    (net (code "43") (name "/USBA_5V") (class "Default")
      (node (ref "ED3") (pin "2") (pinfunction "2_2") (pintype "passive"))
      (node (ref "J1") (pin "1") (pinfunction "+5V_1") (pintype "passive"))
      (node (ref "R30") (pin "1") (pinfunction "1_1") (pintype "passive"))
    )
    (net (code "44") (name "/USBA_N") (class "Default")
      (node (ref "ED2") (pin "2") (pinfunction "2_2") (pintype "passive"))
      (node (ref "J1") (pin "2") (pinfunction "D-_2") (pintype "passive"))
      (node (ref "U4") (pin "5") (pinfunction "D-_5") (pintype "passive"))
    )
    (net (code "45") (name "/USBA_P") (class "Default")
      (node (ref "ED1") (pin "2") (pinfunction "2_2") (pintype "passive"))
      (node (ref "J1") (pin "3") (pinfunction "D+_3") (pintype "passive"))
      (node (ref "U4") (pin "4") (pinfunction "D+_4") (pintype "passive"))
    )
    (net (code "46") (name "/nINT") (class "Default")
      (node (ref "JP4") (pin "7") (pinfunction "7_7") (pintype "passive"))
      (node (ref "R1") (pin "1") (pinfunction "1_1") (pintype "passive"))
      (node (ref "R21") (pin "2") (pinfunction "2_2") (pintype "passive"))
      (node (ref "R4") (pin "2") (pinfunction "2_2") (pintype "passive"))
    )
    (net (code "47") (name "/nINT1") (class "Default")
      (node (ref "R4") (pin "1") (pinfunction "1_1") (pintype "passive"))
      (node (ref "U1") (pin "1") (pinfunction "~{INT}_1") (pintype "passive"))
    )
    (net (code "48") (name "/nINT2") (class "Default")
      (node (ref "R21") (pin "1") (pinfunction "1_1") (pintype "passive"))
      (node (ref "U2") (pin "1") (pinfunction "~{INT}_1") (pintype "passive"))
    )
    (net (code "49") (name "GND") (class "Default")
      (node (ref "C1") (pin "2") (pinfunction "2_2") (pintype "passive"))
      (node (ref "C12") (pin "1") (pintype "passive"))
      (node (ref "C13") (pin "1") (pintype "passive"))
      (node (ref "C14P") (pin "2") (pinfunction "2_2") (pintype "passive"))
      (node (ref "C16P") (pin "2") (pinfunction "2_2") (pintype "passive"))
      (node (ref "C17P") (pin "2") (pinfunction "2_2") (pintype "passive"))
      (node (ref "C18P") (pin "2") (pinfunction "2_2") (pintype "passive"))
      (node (ref "C2") (pin "2") (pinfunction "2_2") (pintype "passive"))
      (node (ref "C3") (pin "2") (pinfunction "2_2") (pintype "passive"))
      (node (ref "C4") (pin "2") (pinfunction "2_2") (pintype "passive"))
      (node (ref "C5") (pin "2") (pinfunction "2_2") (pintype "passive"))
      (node (ref "C6") (pin "2") (pinfunction "2_2") (pintype "passive"))
      (node (ref "C7") (pin "2") (pinfunction "2_2") (pintype "passive"))
      (node (ref "C8") (pin "2") (pinfunction "2_2") (pintype "passive"))
      (node (ref "D3") (pin "K") (pinfunction "K_K") (pintype "passive"))
      (node (ref "ED1") (pin "1") (pinfunction "1_1") (pintype "passive"))
      (node (ref "ED2") (pin "1") (pinfunction "1_1") (pintype "passive"))
      (node (ref "ED3") (pin "1") (pinfunction "1_1") (pintype "passive"))
      (node (ref "ED4") (pin "1") (pinfunction "1_1") (pintype "passive"))
      (node (ref "ED5") (pin "1") (pinfunction "1_1") (pintype "passive"))
      (node (ref "ED6") (pin "1") (pinfunction "1_1") (pintype "passive"))
      (node (ref "J1") (pin "4") (pinfunction "GND_4") (pintype "passive"))
      (node (ref "J1") (pin "5") (pinfunction "PAD_5") (pintype "passive"))
      (node (ref "J1") (pin "6") (pinfunction "PAD_6") (pintype "passive"))
      (node (ref "J2") (pin "4") (pinfunction "GND_4") (pintype "passive"))
      (node (ref "J3") (pin "4") (pinfunction "4_4") (pintype "passive"))
      (node (ref "J4") (pin "4") (pinfunction "4_4") (pintype "passive"))
      (node (ref "J5") (pin "3") (pinfunction "3_3") (pintype "passive"))
      (node (ref "J5") (pin "4") (pinfunction "4_4") (pintype "passive"))
      (node (ref "KEY2") (pin "3") (pinfunction "C_3") (pintype "passive"))
      (node (ref "KEY2") (pin "5") (pinfunction "E_5") (pintype "passive"))
      (node (ref "N1") (pin "E") (pinfunction "E_E") (pintype "passive"))
      (node (ref "N10") (pin "E") (pinfunction "E_E") (pintype "passive"))
      (node (ref "N11") (pin "E") (pinfunction "E_E") (pintype "passive"))
      (node (ref "N12") (pin "E") (pinfunction "E_E") (pintype "passive"))
      (node (ref "N13") (pin "E") (pinfunction "E_E") (pintype "passive"))
      (node (ref "N14") (pin "E") (pinfunction "E_E") (pintype "passive"))
      (node (ref "N15") (pin "E") (pinfunction "E_E") (pintype "passive"))
      (node (ref "N2") (pin "E") (pinfunction "E_E") (pintype "passive"))
      (node (ref "N3") (pin "E") (pinfunction "E_E") (pintype "passive"))
      (node (ref "N4") (pin "E") (pinfunction "E_E") (pintype "passive"))
      (node (ref "N5") (pin "E") (pinfunction "E_E") (pintype "passive"))
      (node (ref "N6") (pin "E") (pinfunction "E_E") (pintype "passive"))
      (node (ref "N7") (pin "E") (pinfunction "E_E") (pintype "passive"))
      (node (ref "N8") (pin "E") (pinfunction "E_E") (pintype "passive"))
      (node (ref "N9") (pin "E") (pinfunction "E_E") (pintype "passive"))
      (node (ref "R18") (pin "2") (pinfunction "2_2") (pintype "passive"))
      (node (ref "R32") (pin "2") (pinfunction "2_2") (pintype "passive"))
      (node (ref "R33") (pin "2") (pinfunction "2_2") (pintype "passive"))
      (node (ref "SW1") (pin "1") (pinfunction "1_1") (pintype "passive"))
      (node (ref "SW10") (pin "1") (pinfunction "1_1") (pintype "passive"))
      (node (ref "SW11") (pin "1") (pinfunction "1_1") (pintype "passive"))
      (node (ref "SW12") (pin "1") (pinfunction "1_1") (pintype "passive"))
      (node (ref "SW13") (pin "1") (pinfunction "1_1") (pintype "passive"))
      (node (ref "SW14") (pin "1") (pinfunction "1_1") (pintype "passive"))
      (node (ref "SW15") (pin "1") (pinfunction "1_1") (pintype "passive"))
      (node (ref "SW2") (pin "1") (pinfunction "1_1") (pintype "passive"))
      (node (ref "SW3") (pin "1") (pinfunction "1_1") (pintype "passive"))
      (node (ref "SW4") (pin "1") (pinfunction "1_1") (pintype "passive"))
      (node (ref "SW5") (pin "1") (pinfunction "1_1") (pintype "passive"))
      (node (ref "SW6") (pin "1") (pinfunction "1_1") (pintype "passive"))
      (node (ref "SW7") (pin "1") (pinfunction "1_1") (pintype "passive"))
      (node (ref "SW8") (pin "1") (pinfunction "1_1") (pintype "passive"))
      (node (ref "SW9") (pin "1") (pinfunction "1_1") (pintype "passive"))
      (node (ref "U1") (pin "12") (pinfunction "GND_12") (pintype "passive"))
      (node (ref "U1") (pin "2") (pinfunction "A1_2") (pintype "passive"))
      (node (ref "U1") (pin "21") (pinfunction "A0_21") (pintype "passive"))
      (node (ref "U1") (pin "3") (pinfunction "A2_3") (pintype "passive"))
      (node (ref "U2") (pin "12") (pinfunction "GND_12") (pintype "passive"))
      (node (ref "U2") (pin "2") (pinfunction "A1_2") (pintype "passive"))
      (node (ref "U2") (pin "3") (pinfunction "A2_3") (pintype "passive"))
      (node (ref "U3") (pin "2") (pinfunction "2_2") (pintype "passive"))
      (node (ref "U4") (pin "29") (pinfunction "PGND_29") (pintype "passive"))
      (node (ref "U4") (pin "3") (pinfunction "GND_3") (pintype "passive"))
    )
    (net (code "50") (name "Net-(C19P-Pad2)") (class "Default")
      (node (ref "C19P") (pin "2") (pinfunction "2_2") (pintype "passive"))
      (node (ref "R16") (pin "2") (pinfunction "2_2") (pintype "passive"))
      (node (ref "R18") (pin "1") (pinfunction "1_1") (pintype "passive"))
      (node (ref "U3") (pin "6") (pinfunction "6_6") (pintype "passive"))
    )
    (net (code "51") (name "Net-(D3-PadA)") (class "Default")
      (node (ref "D3") (pin "A") (pinfunction "A_A") (pintype "passive"))
      (node (ref "R17") (pin "2") (pinfunction "2_2") (pintype "passive"))
    )
    (net (code "52") (name "Net-(JP4-Pad5)") (class "Default")
      (node (ref "JP4") (pin "5") (pinfunction "5_5") (pintype "passive"))
      (node (ref "R32") (pin "1") (pinfunction "1_1") (pintype "passive"))
    )
    (net (code "53") (name "Net-(JP4-Pad6)") (class "Default")
      (node (ref "JP4") (pin "6") (pinfunction "6_6") (pintype "passive"))
      (node (ref "R33") (pin "1") (pinfunction "1_1") (pintype "passive"))
    )
    (net (code "54") (name "Net-(KEY2-A)") (class "Default")
      (node (ref "KEY2") (pin "1") (pinfunction "A_1") (pintype "passive"))
      (node (ref "R6") (pin "1") (pintype "passive"))
      (node (ref "R7") (pin "2") (pintype "passive"))
    )
    (net (code "55") (name "Net-(KEY2-B)") (class "Default")
      (node (ref "KEY2") (pin "2") (pinfunction "B_2") (pintype "passive"))
      (node (ref "R5") (pin "1") (pintype "passive"))
      (node (ref "R9") (pin "2") (pintype "passive"))
    )
    (net (code "56") (name "Net-(KEY2-D)") (class "Default")
      (node (ref "KEY2") (pin "4") (pinfunction "D_4") (pintype "passive"))
      (node (ref "R16W") (pin "1") (pinfunction "1_1") (pintype "passive"))
    )
    (net (code "57") (name "Net-(L1-Pad1)") (class "Default")
      (node (ref "L1") (pin "1") (pinfunction "1_1") (pintype "passive"))
      (node (ref "U3") (pin "3") (pinfunction "3_3") (pintype "passive"))
    )
    (net (code "58") (name "Net-(N1-PadB)") (class "Default")
      (node (ref "N1") (pin "B") (pinfunction "B_B") (pintype "passive"))
      (node (ref "R1E") (pin "2") (pinfunction "2_2") (pintype "passive"))
    )
    (net (code "59") (name "Net-(N1-PadC)") (class "Default")
      (node (ref "N1") (pin "C") (pinfunction "C_C") (pintype "passive"))
      (node (ref "R1D") (pin "2") (pinfunction "2_2") (pintype "passive"))
    )
    (net (code "60") (name "Net-(N2-PadB)") (class "Default")
      (node (ref "N2") (pin "B") (pinfunction "B_B") (pintype "passive"))
      (node (ref "R2E") (pin "2") (pinfunction "2_2") (pintype "passive"))
    )
    (net (code "61") (name "Net-(N2-PadC)") (class "Default")
      (node (ref "N2") (pin "C") (pinfunction "C_C") (pintype "passive"))
      (node (ref "R2D") (pin "2") (pinfunction "2_2") (pintype "passive"))
    )
    (net (code "62") (name "Net-(N3-PadB)") (class "Default")
      (node (ref "N3") (pin "B") (pinfunction "B_B") (pintype "passive"))
      (node (ref "R3E") (pin "2") (pinfunction "2_2") (pintype "passive"))
    )
    (net (code "63") (name "Net-(N3-PadC)") (class "Default")
      (node (ref "N3") (pin "C") (pinfunction "C_C") (pintype "passive"))
      (node (ref "R3D") (pin "2") (pinfunction "2_2") (pintype "passive"))
    )
    (net (code "64") (name "Net-(N4-PadB)") (class "Default")
      (node (ref "N4") (pin "B") (pinfunction "B_B") (pintype "passive"))
      (node (ref "R4E") (pin "2") (pinfunction "2_2") (pintype "passive"))
    )
    (net (code "65") (name "Net-(N4-PadC)") (class "Default")
      (node (ref "N4") (pin "C") (pinfunction "C_C") (pintype "passive"))
      (node (ref "R4D") (pin "2") (pinfunction "2_2") (pintype "passive"))
    )
    (net (code "66") (name "Net-(N5-PadB)") (class "Default")
      (node (ref "N5") (pin "B") (pinfunction "B_B") (pintype "passive"))
      (node (ref "R5E") (pin "2") (pinfunction "2_2") (pintype "passive"))
    )
    (net (code "67") (name "Net-(N5-PadC)") (class "Default")
      (node (ref "N5") (pin "C") (pinfunction "C_C") (pintype "passive"))
      (node (ref "R5D") (pin "2") (pinfunction "2_2") (pintype "passive"))
    )
    (net (code "68") (name "Net-(N6-PadB)") (class "Default")
      (node (ref "N6") (pin "B") (pinfunction "B_B") (pintype "passive"))
      (node (ref "R6E") (pin "2") (pinfunction "2_2") (pintype "passive"))
    )
    (net (code "69") (name "Net-(N6-PadC)") (class "Default")
      (node (ref "N6") (pin "C") (pinfunction "C_C") (pintype "passive"))
      (node (ref "R6D") (pin "2") (pinfunction "2_2") (pintype "passive"))
    )
    (net (code "70") (name "Net-(N7-PadB)") (class "Default")
      (node (ref "N7") (pin "B") (pinfunction "B_B") (pintype "passive"))
      (node (ref "R7E") (pin "2") (pinfunction "2_2") (pintype "passive"))
    )
    (net (code "71") (name "Net-(N7-PadC)") (class "Default")
      (node (ref "N7") (pin "C") (pinfunction "C_C") (pintype "passive"))
      (node (ref "R7D") (pin "2") (pinfunction "2_2") (pintype "passive"))
    )
    (net (code "72") (name "Net-(N8-PadB)") (class "Default")
      (node (ref "N8") (pin "B") (pinfunction "B_B") (pintype "passive"))
      (node (ref "R8E") (pin "2") (pinfunction "2_2") (pintype "passive"))
    )
    (net (code "73") (name "Net-(N8-PadC)") (class "Default")
      (node (ref "N8") (pin "C") (pinfunction "C_C") (pintype "passive"))
      (node (ref "R8D") (pin "2") (pinfunction "2_2") (pintype "passive"))
    )
    (net (code "74") (name "Net-(N9-PadB)") (class "Default")
      (node (ref "N9") (pin "B") (pinfunction "B_B") (pintype "passive"))
      (node (ref "R9E") (pin "2") (pinfunction "2_2") (pintype "passive"))
    )
    (net (code "75") (name "Net-(N9-PadC)") (class "Default")
      (node (ref "N9") (pin "C") (pinfunction "C_C") (pintype "passive"))
      (node (ref "R9D") (pin "2") (pinfunction "2_2") (pintype "passive"))
    )
    (net (code "76") (name "Net-(N10-PadB)") (class "Default")
      (node (ref "N10") (pin "B") (pinfunction "B_B") (pintype "passive"))
      (node (ref "R10E") (pin "2") (pinfunction "2_2") (pintype "passive"))
    )
    (net (code "77") (name "Net-(N10-PadC)") (class "Default")
      (node (ref "N10") (pin "C") (pinfunction "C_C") (pintype "passive"))
      (node (ref "R10D") (pin "2") (pinfunction "2_2") (pintype "passive"))
    )
    (net (code "78") (name "Net-(N11-PadB)") (class "Default")
      (node (ref "N11") (pin "B") (pinfunction "B_B") (pintype "passive"))
      (node (ref "R11E") (pin "2") (pinfunction "2_2") (pintype "passive"))
    )
    (net (code "79") (name "Net-(N11-PadC)") (class "Default")
      (node (ref "N11") (pin "C") (pinfunction "C_C") (pintype "passive"))
      (node (ref "R11D") (pin "2") (pinfunction "2_2") (pintype "passive"))
    )
    (net (code "80") (name "Net-(N12-PadB)") (class "Default")
      (node (ref "N12") (pin "B") (pinfunction "B_B") (pintype "passive"))
      (node (ref "R12E") (pin "2") (pinfunction "2_2") (pintype "passive"))
    )
    (net (code "81") (name "Net-(N12-PadC)") (class "Default")
      (node (ref "N12") (pin "C") (pinfunction "C_C") (pintype "passive"))
      (node (ref "R12D") (pin "2") (pinfunction "2_2") (pintype "passive"))
    )
    (net (code "82") (name "Net-(N13-PadB)") (class "Default")
      (node (ref "N13") (pin "B") (pinfunction "B_B") (pintype "passive"))
      (node (ref "R13E") (pin "2") (pinfunction "2_2") (pintype "passive"))
    )
    (net (code "83") (name "Net-(N13-PadC)") (class "Default")
      (node (ref "N13") (pin "C") (pinfunction "C_C") (pintype "passive"))
      (node (ref "R13D") (pin "2") (pinfunction "2_2") (pintype "passive"))
    )
    (net (code "84") (name "Net-(N14-PadB)") (class "Default")
      (node (ref "N14") (pin "B") (pinfunction "B_B") (pintype "passive"))
      (node (ref "R14E") (pin "2") (pinfunction "2_2") (pintype "passive"))
    )
    (net (code "85") (name "Net-(N14-PadC)") (class "Default")
      (node (ref "N14") (pin "C") (pinfunction "C_C") (pintype "passive"))
      (node (ref "R14D") (pin "2") (pinfunction "2_2") (pintype "passive"))
    )
    (net (code "86") (name "Net-(N15-PadB)") (class "Default")
      (node (ref "N15") (pin "B") (pinfunction "B_B") (pintype "passive"))
      (node (ref "R15E") (pin "2") (pinfunction "2_2") (pintype "passive"))
    )
    (net (code "87") (name "Net-(N15-PadC)") (class "Default")
      (node (ref "N15") (pin "C") (pinfunction "C_C") (pintype "passive"))
      (node (ref "R15D") (pin "2") (pinfunction "2_2") (pintype "passive"))
    )
    (net (code "88") (name "Net-(R1D-Pad1)") (class "Default")
      (node (ref "R1D") (pin "1") (pinfunction "1_1") (pintype "passive"))
      (node (ref "SW1") (pin "5") (pinfunction "5_5") (pintype "passive"))
    )
    (net (code "89") (name "Net-(R1W-Pad1)") (class "Default")
      (node (ref "R1W") (pin "1") (pinfunction "1_1") (pintype "passive"))
      (node (ref "SW1") (pin "2") (pinfunction "2_2") (pintype "passive"))
    )
    (net (code "90") (name "Net-(R2D-Pad1)") (class "Default")
      (node (ref "R2D") (pin "1") (pinfunction "1_1") (pintype "passive"))
      (node (ref "SW2") (pin "5") (pinfunction "5_5") (pintype "passive"))
    )
    (net (code "91") (name "Net-(R2W-Pad1)") (class "Default")
      (node (ref "R2W") (pin "1") (pinfunction "1_1") (pintype "passive"))
      (node (ref "SW2") (pin "2") (pinfunction "2_2") (pintype "passive"))
    )
    (net (code "92") (name "Net-(R3D-Pad1)") (class "Default")
      (node (ref "R3D") (pin "1") (pinfunction "1_1") (pintype "passive"))
      (node (ref "SW3") (pin "5") (pinfunction "5_5") (pintype "passive"))
    )
    (net (code "93") (name "Net-(R3W-Pad1)") (class "Default")
      (node (ref "R3W") (pin "1") (pinfunction "1_1") (pintype "passive"))
      (node (ref "SW3") (pin "2") (pinfunction "2_2") (pintype "passive"))
    )
    (net (code "94") (name "Net-(R4D-Pad1)") (class "Default")
      (node (ref "R4D") (pin "1") (pinfunction "1_1") (pintype "passive"))
      (node (ref "SW4") (pin "5") (pinfunction "5_5") (pintype "passive"))
    )
    (net (code "95") (name "Net-(R4W-Pad1)") (class "Default")
      (node (ref "R4W") (pin "1") (pinfunction "1_1") (pintype "passive"))
      (node (ref "SW4") (pin "2") (pinfunction "2_2") (pintype "passive"))
    )
    (net (code "96") (name "Net-(R5D-Pad1)") (class "Default")
      (node (ref "R5D") (pin "1") (pinfunction "1_1") (pintype "passive"))
      (node (ref "SW5") (pin "5") (pinfunction "5_5") (pintype "passive"))
    )
    (net (code "97") (name "Net-(R5W-Pad1)") (class "Default")
      (node (ref "R5W") (pin "1") (pinfunction "1_1") (pintype "passive"))
      (node (ref "SW5") (pin "2") (pinfunction "2_2") (pintype "passive"))
    )
    (net (code "98") (name "Net-(R6D-Pad1)") (class "Default")
      (node (ref "R6D") (pin "1") (pinfunction "1_1") (pintype "passive"))
      (node (ref "SW6") (pin "5") (pinfunction "5_5") (pintype "passive"))
    )
    (net (code "99") (name "Net-(R6W-Pad1)") (class "Default")
      (node (ref "R6W") (pin "1") (pinfunction "1_1") (pintype "passive"))
      (node (ref "SW6") (pin "2") (pinfunction "2_2") (pintype "passive"))
    )
    (net (code "100") (name "Net-(R7D-Pad1)") (class "Default")
      (node (ref "R7D") (pin "1") (pinfunction "1_1") (pintype "passive"))
      (node (ref "SW7") (pin "5") (pinfunction "5_5") (pintype "passive"))
    )
    (net (code "101") (name "Net-(R7W-Pad1)") (class "Default")
      (node (ref "R7W") (pin "1") (pinfunction "1_1") (pintype "passive"))
      (node (ref "SW7") (pin "2") (pinfunction "2_2") (pintype "passive"))
    )
    (net (code "102") (name "Net-(R8D-Pad1)") (class "Default")
      (node (ref "R8D") (pin "1") (pinfunction "1_1") (pintype "passive"))
      (node (ref "SW8") (pin "5") (pinfunction "5_5") (pintype "passive"))
    )
    (net (code "103") (name "Net-(R8W-Pad1)") (class "Default")
      (node (ref "R8W") (pin "1") (pinfunction "1_1") (pintype "passive"))
      (node (ref "SW8") (pin "2") (pinfunction "2_2") (pintype "passive"))
    )
    (net (code "104") (name "Net-(R9D-Pad1)") (class "Default")
      (node (ref "R9D") (pin "1") (pinfunction "1_1") (pintype "passive"))
      (node (ref "SW9") (pin "5") (pinfunction "5_5") (pintype "passive"))
    )
    (net (code "105") (name "Net-(R9W-Pad1)") (class "Default")
      (node (ref "R9W") (pin "1") (pinfunction "1_1") (pintype "passive"))
      (node (ref "SW9") (pin "2") (pinfunction "2_2") (pintype "passive"))
    )
    (net (code "106") (name "Net-(R10D-Pad1)") (class "Default")
      (node (ref "R10D") (pin "1") (pinfunction "1_1") (pintype "passive"))
      (node (ref "SW10") (pin "5") (pinfunction "5_5") (pintype "passive"))
    )
    (net (code "107") (name "Net-(R10W-Pad1)") (class "Default")
      (node (ref "R10W") (pin "1") (pinfunction "1_1") (pintype "passive"))
      (node (ref "SW10") (pin "2") (pinfunction "2_2") (pintype "passive"))
    )
    (net (code "108") (name "Net-(R11D-Pad1)") (class "Default")
      (node (ref "R11D") (pin "1") (pinfunction "1_1") (pintype "passive"))
      (node (ref "SW11") (pin "5") (pinfunction "5_5") (pintype "passive"))
    )
    (net (code "109") (name "Net-(R11W-Pad1)") (class "Default")
      (node (ref "R11W") (pin "1") (pinfunction "1_1") (pintype "passive"))
      (node (ref "SW11") (pin "2") (pinfunction "2_2") (pintype "passive"))
    )
    (net (code "110") (name "Net-(R12D-Pad1)") (class "Default")
      (node (ref "R12D") (pin "1") (pinfunction "1_1") (pintype "passive"))
      (node (ref "SW12") (pin "5") (pinfunction "5_5") (pintype "passive"))
    )
    (net (code "111") (name "Net-(R12W-Pad1)") (class "Default")
      (node (ref "R12W") (pin "1") (pinfunction "1_1") (pintype "passive"))
      (node (ref "SW12") (pin "2") (pinfunction "2_2") (pintype "passive"))
    )
    (net (code "112") (name "Net-(R13D-Pad1)") (class "Default")
      (node (ref "R13D") (pin "1") (pinfunction "1_1") (pintype "passive"))
      (node (ref "SW13") (pin "5") (pinfunction "5_5") (pintype "passive"))
    )
    (net (code "113") (name "Net-(R13W-Pad1)") (class "Default")
      (node (ref "R13W") (pin "1") (pinfunction "1_1") (pintype "passive"))
      (node (ref "SW13") (pin "2") (pinfunction "2_2") (pintype "passive"))
    )
    (net (code "114") (name "Net-(R14D-Pad1)") (class "Default")
      (node (ref "R14D") (pin "1") (pinfunction "1_1") (pintype "passive"))
      (node (ref "SW14") (pin "5") (pinfunction "5_5") (pintype "passive"))
    )
    (net (code "115") (name "Net-(R14W-Pad1)") (class "Default")
      (node (ref "R14W") (pin "1") (pinfunction "1_1") (pintype "passive"))
      (node (ref "SW14") (pin "2") (pinfunction "2_2") (pintype "passive"))
    )
    (net (code "116") (name "Net-(R15D-Pad1)") (class "Default")
      (node (ref "R15D") (pin "1") (pinfunction "1_1") (pintype "passive"))
      (node (ref "SW15") (pin "5") (pinfunction "5_5") (pintype "passive"))
    )
    (net (code "117") (name "Net-(R15W-Pad1)") (class "Default")
      (node (ref "R15W") (pin "1") (pinfunction "1_1") (pintype "passive"))
      (node (ref "SW15") (pin "2") (pinfunction "2_2") (pintype "passive"))
    )
    (net (code "118") (name "Net-(U4-REGIN)") (class "Default")
      (node (ref "C2") (pin "1") (pinfunction "1_1") (pintype "passive"))
      (node (ref "C3") (pin "1") (pinfunction "1_1") (pintype "passive"))
      (node (ref "U4") (pin "7") (pinfunction "REGIN_7") (pintype "passive"))
      (node (ref "U4") (pin "8") (pinfunction "VBUS_8") (pintype "passive"))
    )
    (net (code "119") (name "Net-(U4-RXD)") (class "Default")
      (node (ref "R27") (pin "2") (pinfunction "2_2") (pintype "passive"))
      (node (ref "U4") (pin "25") (pinfunction "RXD_25") (pintype "passive"))
    )
    (net (code "120") (name "Net-(U4-TXD)") (class "Default")
      (node (ref "R26") (pin "2") (pinfunction "2_2") (pintype "passive"))
      (node (ref "U4") (pin "26") (pinfunction "TXD_26") (pintype "passive"))
    )
    (net (code "121") (name "Net-(U4-VDD)") (class "Default")
      (node (ref "C1") (pin "1") (pinfunction "1_1") (pintype "passive"))
      (node (ref "R25") (pin "2") (pinfunction "2_2") (pintype "passive"))
      (node (ref "U4") (pin "6") (pinfunction "VDD_6") (pintype "passive"))
    )
    (net (code "122") (name "Net-(U4-~{RST})") (class "Default")
      (node (ref "C4") (pin "1") (pinfunction "1_1") (pintype "passive"))
      (node (ref "R25") (pin "1") (pinfunction "1_1") (pintype "passive"))
      (node (ref "U4") (pin "9") (pinfunction "~{RST}_9") (pintype "passive"))
    )
    (net (code "123") (name "VCC") (class "Default")
      (node (ref "C17P") (pin "1") (pinfunction "1_1") (pintype "passive"))
      (node (ref "C18P") (pin "1") (pinfunction "1_1") (pintype "passive"))
      (node (ref "C5") (pin "1") (pinfunction "1_1") (pintype "passive"))
      (node (ref "C6") (pin "1") (pinfunction "1_1") (pintype "passive"))
      (node (ref "C7") (pin "1") (pinfunction "1_1") (pintype "passive"))
      (node (ref "C8") (pin "1") (pinfunction "1_1") (pintype "passive"))
      (node (ref "J3") (pin "1") (pinfunction "1_1") (pintype "passive"))
      (node (ref "J4") (pin "1") (pinfunction "1_1") (pintype "passive"))
      (node (ref "J5") (pin "1") (pinfunction "1_1") (pintype "passive"))
      (node (ref "J5") (pin "2") (pinfunction "2_2") (pintype "passive"))
      (node (ref "R30") (pin "2") (pinfunction "2_2") (pintype "passive"))
      (node (ref "R31") (pin "2") (pinfunction "2_2") (pintype "passive"))
      (node (ref "RP1") (pin "5") (pinfunction "5_5") (pintype "passive"))
      (node (ref "RP1") (pin "6") (pinfunction "6_6") (pintype "passive"))
      (node (ref "RP1") (pin "7") (pinfunction "7_7") (pintype "passive"))
      (node (ref "RP1") (pin "8") (pinfunction "8_8") (pintype "passive"))
      (node (ref "RP2") (pin "5") (pinfunction "5_5") (pintype "passive"))
      (node (ref "RP2") (pin "6") (pinfunction "6_6") (pintype "passive"))
      (node (ref "RP2") (pin "7") (pinfunction "7_7") (pintype "passive"))
      (node (ref "RP2") (pin "8") (pinfunction "8_8") (pintype "passive"))
      (node (ref "RP3") (pin "5") (pinfunction "5_5") (pintype "passive"))
      (node (ref "RP3") (pin "6") (pinfunction "6_6") (pintype "passive"))
      (node (ref "RP3") (pin "7") (pinfunction "7_7") (pintype "passive"))
      (node (ref "RP3") (pin "8") (pinfunction "8_8") (pintype "passive"))
      (node (ref "RP4") (pin "5") (pinfunction "5_5") (pintype "passive"))
      (node (ref "RP4") (pin "6") (pinfunction "6_6") (pintype "passive"))
      (node (ref "RP4") (pin "7") (pinfunction "7_7") (pintype "passive"))
      (node (ref "RP4") (pin "8") (pinfunction "8_8") (pintype "passive"))
      (node (ref "RP5") (pin "5") (pinfunction "5_5") (pintype "passive"))
      (node (ref "RP5") (pin "6") (pinfunction "6_6") (pintype "passive"))
      (node (ref "RP5") (pin "7") (pinfunction "7_7") (pintype "passive"))
      (node (ref "RP5") (pin "8") (pinfunction "8_8") (pintype "passive"))
      (node (ref "RP6") (pin "5") (pinfunction "5_5") (pintype "passive"))
      (node (ref "RP6") (pin "6") (pinfunction "6_6") (pintype "passive"))
      (node (ref "RP6") (pin "7") (pinfunction "7_7") (pintype "passive"))
      (node (ref "RP6") (pin "8") (pinfunction "8_8") (pintype "passive"))
      (node (ref "RP7") (pin "5") (pinfunction "5_5") (pintype "passive"))
      (node (ref "RP7") (pin "6") (pinfunction "6_6") (pintype "passive"))
      (node (ref "RP7") (pin "7") (pinfunction "7_7") (pintype "passive"))
      (node (ref "RP7") (pin "8") (pinfunction "8_8") (pintype "passive"))
      (node (ref "RP8") (pin "5") (pinfunction "5_5") (pintype "passive"))
      (node (ref "RP8") (pin "6") (pinfunction "6_6") (pintype "passive"))
      (node (ref "RP8") (pin "7") (pinfunction "7_7") (pintype "passive"))
      (node (ref "RP8") (pin "8") (pinfunction "8_8") (pintype "passive"))
      (node (ref "SW1") (pin "4") (pinfunction "4_4") (pintype "passive"))
      (node (ref "SW10") (pin "4") (pinfunction "4_4") (pintype "passive"))
      (node (ref "SW11") (pin "4") (pinfunction "4_4") (pintype "passive"))
      (node (ref "SW12") (pin "4") (pinfunction "4_4") (pintype "passive"))
      (node (ref "SW13") (pin "4") (pinfunction "4_4") (pintype "passive"))
      (node (ref "SW14") (pin "4") (pinfunction "4_4") (pintype "passive"))
      (node (ref "SW15") (pin "4") (pinfunction "4_4") (pintype "passive"))
      (node (ref "SW2") (pin "4") (pinfunction "4_4") (pintype "passive"))
      (node (ref "SW3") (pin "4") (pinfunction "4_4") (pintype "passive"))
      (node (ref "SW4") (pin "4") (pinfunction "4_4") (pintype "passive"))
      (node (ref "SW5") (pin "4") (pinfunction "4_4") (pintype "passive"))
      (node (ref "SW6") (pin "4") (pinfunction "4_4") (pintype "passive"))
      (node (ref "SW7") (pin "4") (pinfunction "4_4") (pintype "passive"))
      (node (ref "SW8") (pin "4") (pinfunction "4_4") (pintype "passive"))
      (node (ref "SW9") (pin "4") (pinfunction "4_4") (pintype "passive"))
      (node (ref "U1") (pin "24") (pinfunction "VCC_24") (pintype "passive"))
      (node (ref "U2") (pin "21") (pinfunction "A0_21") (pintype "passive"))
      (node (ref "U2") (pin "24") (pinfunction "VCC_24") (pintype "passive"))
      (node (ref "U3") (pin "1") (pinfunction "1_1") (pintype "passive"))
      (node (ref "U3") (pin "4") (pinfunction "4_4") (pintype "passive"))
    )
    (net (code "124") (name "VCC3.3") (class "Default")
      (node (ref "C14P") (pin "1") (pinfunction "1_1") (pintype "passive"))
      (node (ref "C16P") (pin "1") (pinfunction "1_1") (pintype "passive"))
      (node (ref "C19P") (pin "1") (pinfunction "1_1") (pintype "passive"))
      (node (ref "L1") (pin "2") (pinfunction "2_2") (pintype "passive"))
      (node (ref "R1") (pin "2") (pinfunction "2_2") (pintype "passive"))
      (node (ref "R16") (pin "1") (pinfunction "1_1") (pintype "passive"))
      (node (ref "R17") (pin "1") (pinfunction "1_1") (pintype "passive"))
      (node (ref "R2") (pin "2") (pinfunction "2_2") (pintype "passive"))
      (node (ref "R3") (pin "2") (pinfunction "2_2") (pintype "passive"))
      (node (ref "R5") (pin "2") (pintype "passive"))
      (node (ref "R6") (pin "2") (pintype "passive"))
    )
    (net (code "125") (name "unconnected-(JP4-Pad8)") (class "Default")
      (node (ref "JP4") (pin "8") (pinfunction "8_8") (pintype "passive"))
    )
    (net (code "126") (name "unconnected-(JP4-Pad9)") (class "Default")
      (node (ref "JP4") (pin "9") (pinfunction "9_9") (pintype "passive"))
    )
    (net (code "127") (name "unconnected-(JP4-Pad10)") (class "Default")
      (node (ref "JP4") (pin "10") (pinfunction "10_10") (pintype "passive"))
    )
    (net (code "128") (name "unconnected-(JP4-Pad11)") (class "Default")
      (node (ref "JP4") (pin "11") (pinfunction "11_11") (pintype "passive"))
    )
    (net (code "129") (name "unconnected-(JP4-Pad12)") (class "Default")
      (node (ref "JP4") (pin "12") (pinfunction "12_12") (pintype "passive"))
    )
    (net (code "130") (name "unconnected-(JP4-Pad13)") (class "Default")
      (node (ref "JP4") (pin "13") (pinfunction "13_13") (pintype "passive"))
    )
    (net (code "131") (name "unconnected-(JP4-Pad14)") (class "Default")
      (node (ref "JP4") (pin "14") (pinfunction "14_14") (pintype "passive"))
    )
    (net (code "132") (name "unconnected-(JP4-Pad15)") (class "Default")
      (node (ref "JP4") (pin "15") (pinfunction "15_15") (pintype "passive"))
    )
    (net (code "133") (name "unconnected-(JP4-Pad16)") (class "Default")
      (node (ref "JP4") (pin "16") (pinfunction "16_16") (pintype "passive"))
    )
    (net (code "134") (name "unconnected-(RP8-Pad4)") (class "Default")
      (node (ref "RP8") (pin "4") (pinfunction "4_4") (pintype "passive"))
    )
    (net (code "135") (name "unconnected-(SW1-Pad3)") (class "Default")
      (node (ref "SW1") (pin "3") (pinfunction "3_3") (pintype "passive"))
    )
    (net (code "136") (name "unconnected-(SW2-Pad3)") (class "Default")
      (node (ref "SW2") (pin "3") (pinfunction "3_3") (pintype "passive"))
    )
    (net (code "137") (name "unconnected-(SW3-Pad3)") (class "Default")
      (node (ref "SW3") (pin "3") (pinfunction "3_3") (pintype "passive"))
    )
    (net (code "138") (name "unconnected-(SW4-Pad3)") (class "Default")
      (node (ref "SW4") (pin "3") (pinfunction "3_3") (pintype "passive"))
    )
    (net (code "139") (name "unconnected-(SW5-Pad3)") (class "Default")
      (node (ref "SW5") (pin "3") (pinfunction "3_3") (pintype "passive"))
    )
    (net (code "140") (name "unconnected-(SW6-Pad3)") (class "Default")
      (node (ref "SW6") (pin "3") (pinfunction "3_3") (pintype "passive"))
    )
    (net (code "141") (name "unconnected-(SW7-Pad3)") (class "Default")
      (node (ref "SW7") (pin "3") (pinfunction "3_3") (pintype "passive"))
    )
    (net (code "142") (name "unconnected-(SW8-Pad3)") (class "Default")
      (node (ref "SW8") (pin "3") (pinfunction "3_3") (pintype "passive"))
    )
    (net (code "143") (name "unconnected-(SW9-Pad3)") (class "Default")
      (node (ref "SW9") (pin "3") (pinfunction "3_3") (pintype "passive"))
    )
    (net (code "144") (name "unconnected-(SW10-Pad3)") (class "Default")
      (node (ref "SW10") (pin "3") (pinfunction "3_3") (pintype "passive"))
    )
    (net (code "145") (name "unconnected-(SW11-Pad3)") (class "Default")
      (node (ref "SW11") (pin "3") (pinfunction "3_3") (pintype "passive"))
    )
    (net (code "146") (name "unconnected-(SW12-Pad3)") (class "Default")
      (node (ref "SW12") (pin "3") (pinfunction "3_3") (pintype "passive"))
    )
    (net (code "147") (name "unconnected-(SW13-Pad3)") (class "Default")
      (node (ref "SW13") (pin "3") (pinfunction "3_3") (pintype "passive"))
    )
    (net (code "148") (name "unconnected-(SW14-Pad3)") (class "Default")
      (node (ref "SW14") (pin "3") (pinfunction "3_3") (pintype "passive"))
    )
    (net (code "149") (name "unconnected-(SW15-Pad3)") (class "Default")
      (node (ref "SW15") (pin "3") (pinfunction "3_3") (pintype "passive"))
    )
    (net (code "150") (name "unconnected-(SW16-Pad1)") (class "Default")
      (node (ref "SW16") (pin "1") (pinfunction "1_1") (pintype "passive"))
    )
    (net (code "151") (name "unconnected-(SW16-Pad2)") (class "Default")
      (node (ref "SW16") (pin "2") (pinfunction "2_2") (pintype "passive"))
    )
    (net (code "152") (name "unconnected-(SW16-Pad3)") (class "Default")
      (node (ref "SW16") (pin "3") (pinfunction "3_3") (pintype "passive"))
    )
    (net (code "153") (name "unconnected-(SW16-Pad4)") (class "Default")
      (node (ref "SW16") (pin "4") (pinfunction "4_4") (pintype "passive"))
    )
    (net (code "154") (name "unconnected-(SW16-Pad5)") (class "Default")
      (node (ref "SW16") (pin "5") (pinfunction "5_5") (pintype "passive"))
    )
    (net (code "155") (name "unconnected-(U2-P17-Pad20)") (class "Default")
      (node (ref "U2") (pin "20") (pinfunction "P17_20") (pintype "passive+no_connect"))
    )
    (net (code "156") (name "unconnected-(U3-Pad5)") (class "Default")
      (node (ref "U3") (pin "5") (pinfunction "5_5") (pintype "passive"))
    )
    (net (code "157") (name "unconnected-(U4-CTS-Pad23)") (class "Default")
      (node (ref "U4") (pin "23") (pinfunction "CTS_23") (pintype "passive+no_connect"))
    )
    (net (code "158") (name "unconnected-(U4-DCD-Pad1)") (class "Default")
      (node (ref "U4") (pin "1") (pinfunction "DCD_1") (pintype "passive+no_connect"))
    )
    (net (code "159") (name "unconnected-(U4-DSR-Pad27)") (class "Default")
      (node (ref "U4") (pin "27") (pinfunction "DSR_27") (pintype "passive+no_connect"))
    )
    (net (code "160") (name "unconnected-(U4-DTR-Pad28)") (class "Default")
      (node (ref "U4") (pin "28") (pinfunction "DTR_28") (pintype "passive+no_connect"))
    )
    (net (code "161") (name "unconnected-(U4-NC-Pad10)") (class "Default")
      (node (ref "U4") (pin "10") (pinfunction "NC_10") (pintype "passive+no_connect"))
    )
    (net (code "162") (name "unconnected-(U4-NC-Pad13)") (class "Default")
      (node (ref "U4") (pin "13") (pinfunction "NC_13") (pintype "passive+no_connect"))
    )
    (net (code "163") (name "unconnected-(U4-NC-Pad14)") (class "Default")
      (node (ref "U4") (pin "14") (pinfunction "NC_14") (pintype "passive+no_connect"))
    )
    (net (code "164") (name "unconnected-(U4-NC-Pad15)") (class "Default")
      (node (ref "U4") (pin "15") (pinfunction "NC_15") (pintype "passive+no_connect"))
    )
    (net (code "165") (name "unconnected-(U4-NC-Pad16)") (class "Default")
      (node (ref "U4") (pin "16") (pinfunction "NC_16") (pintype "passive+no_connect"))
    )
    (net (code "166") (name "unconnected-(U4-NC-Pad17)") (class "Default")
      (node (ref "U4") (pin "17") (pinfunction "NC_17") (pintype "passive+no_connect"))
    )
    (net (code "167") (name "unconnected-(U4-NC-Pad18)") (class "Default")
      (node (ref "U4") (pin "18") (pinfunction "NC_18") (pintype "passive+no_connect"))
    )
    (net (code "168") (name "unconnected-(U4-NC-Pad19)") (class "Default")
      (node (ref "U4") (pin "19") (pinfunction "NC_19") (pintype "passive+no_connect"))
    )
    (net (code "169") (name "unconnected-(U4-NC-Pad20)") (class "Default")
      (node (ref "U4") (pin "20") (pinfunction "NC_20") (pintype "passive+no_connect"))
    )
    (net (code "170") (name "unconnected-(U4-NC-Pad21)") (class "Default")
      (node (ref "U4") (pin "21") (pinfunction "NC_21") (pintype "passive+no_connect"))
    )
    (net (code "171") (name "unconnected-(U4-NC-Pad22)") (class "Default")
      (node (ref "U4") (pin "22") (pinfunction "NC_22") (pintype "passive+no_connect"))
    )
    (net (code "172") (name "unconnected-(U4-RI-Pad2)") (class "Default")
      (node (ref "U4") (pin "2") (pinfunction "RI_2") (pintype "passive+no_connect"))
    )
    (net (code "173") (name "unconnected-(U4-RTS-Pad24)") (class "Default")
      (node (ref "U4") (pin "24") (pinfunction "RTS_24") (pintype "passive+no_connect"))
    )
    (net (code "174") (name "unconnected-(U4-SUSPEND-Pad12)") (class "Default")
      (node (ref "U4") (pin "12") (pinfunction "SUSPEND_12") (pintype "passive+no_connect"))
    )
    (net (code "175") (name "unconnected-(U4-~{SUSPEND}-Pad11)") (class "Default")
      (node (ref "U4") (pin "11") (pinfunction "~{SUSPEND}_11") (pintype "passive+no_connect"))
    )
  )
)
